# design.net
KiCad netlist of a schematic drawn in Altium Designer
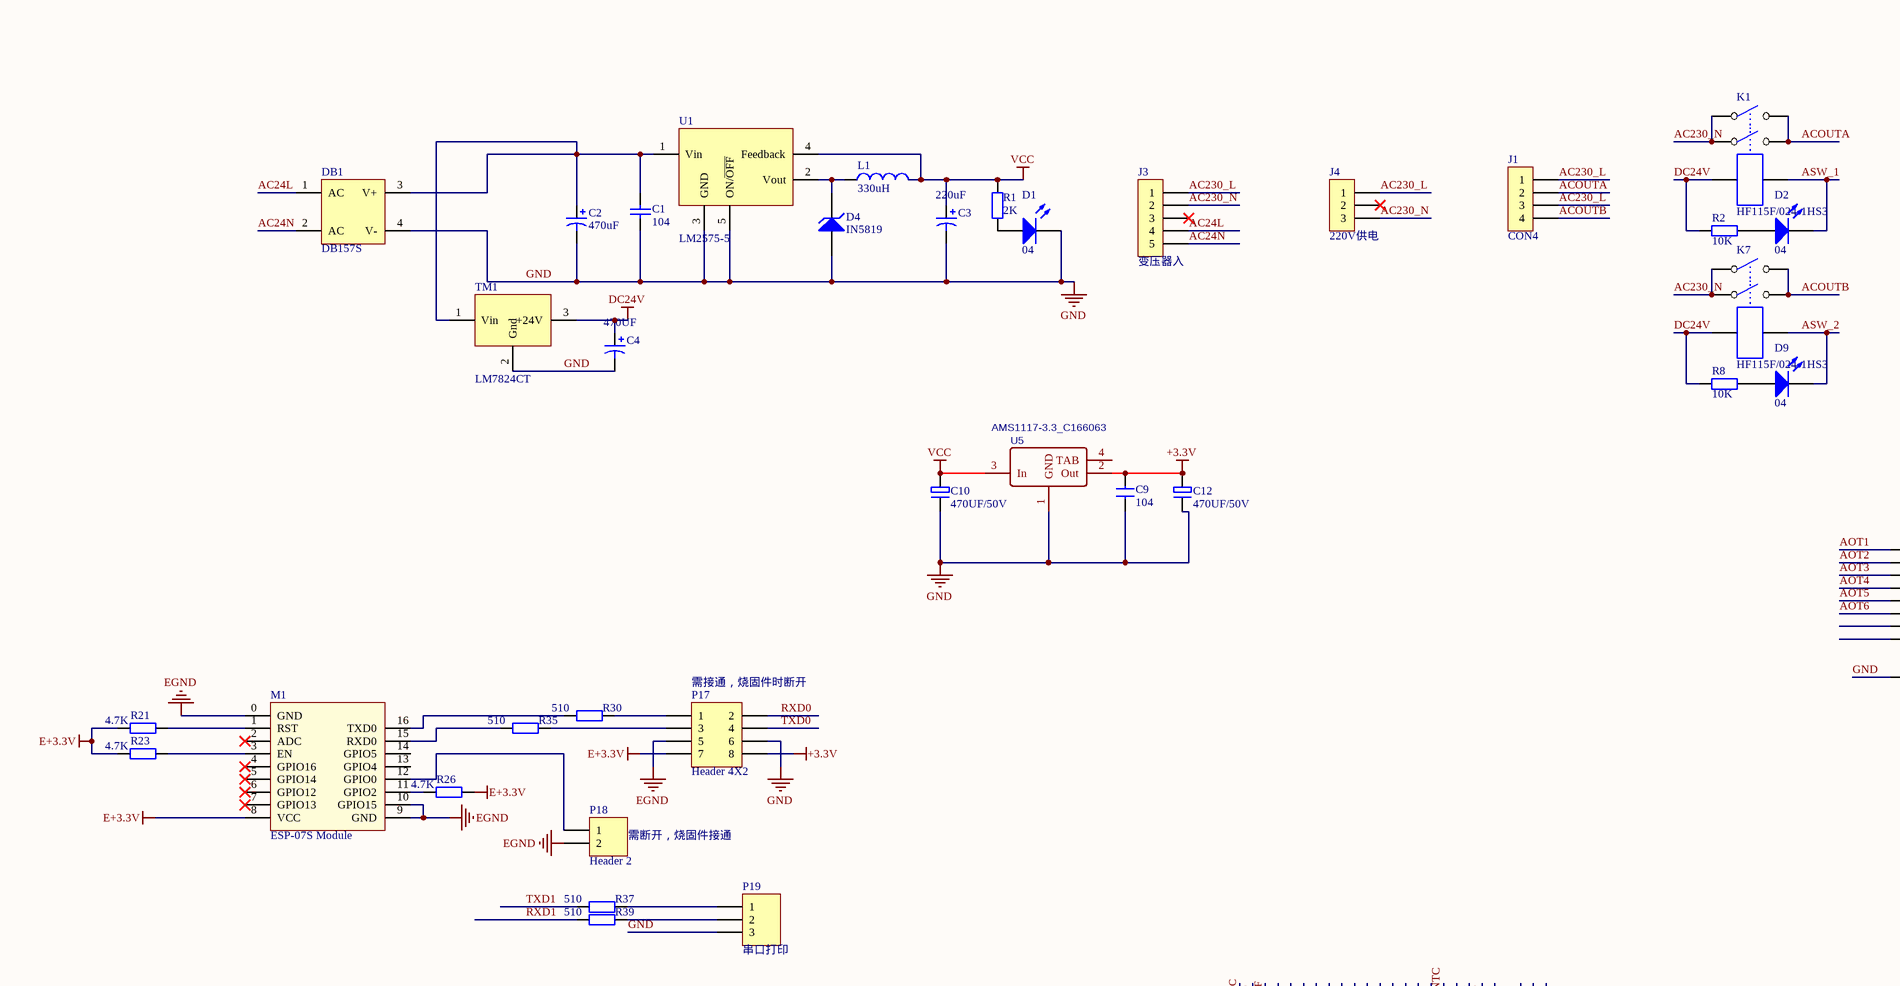
[diagram p0: 下程序炸炉.SchDoc, top left]
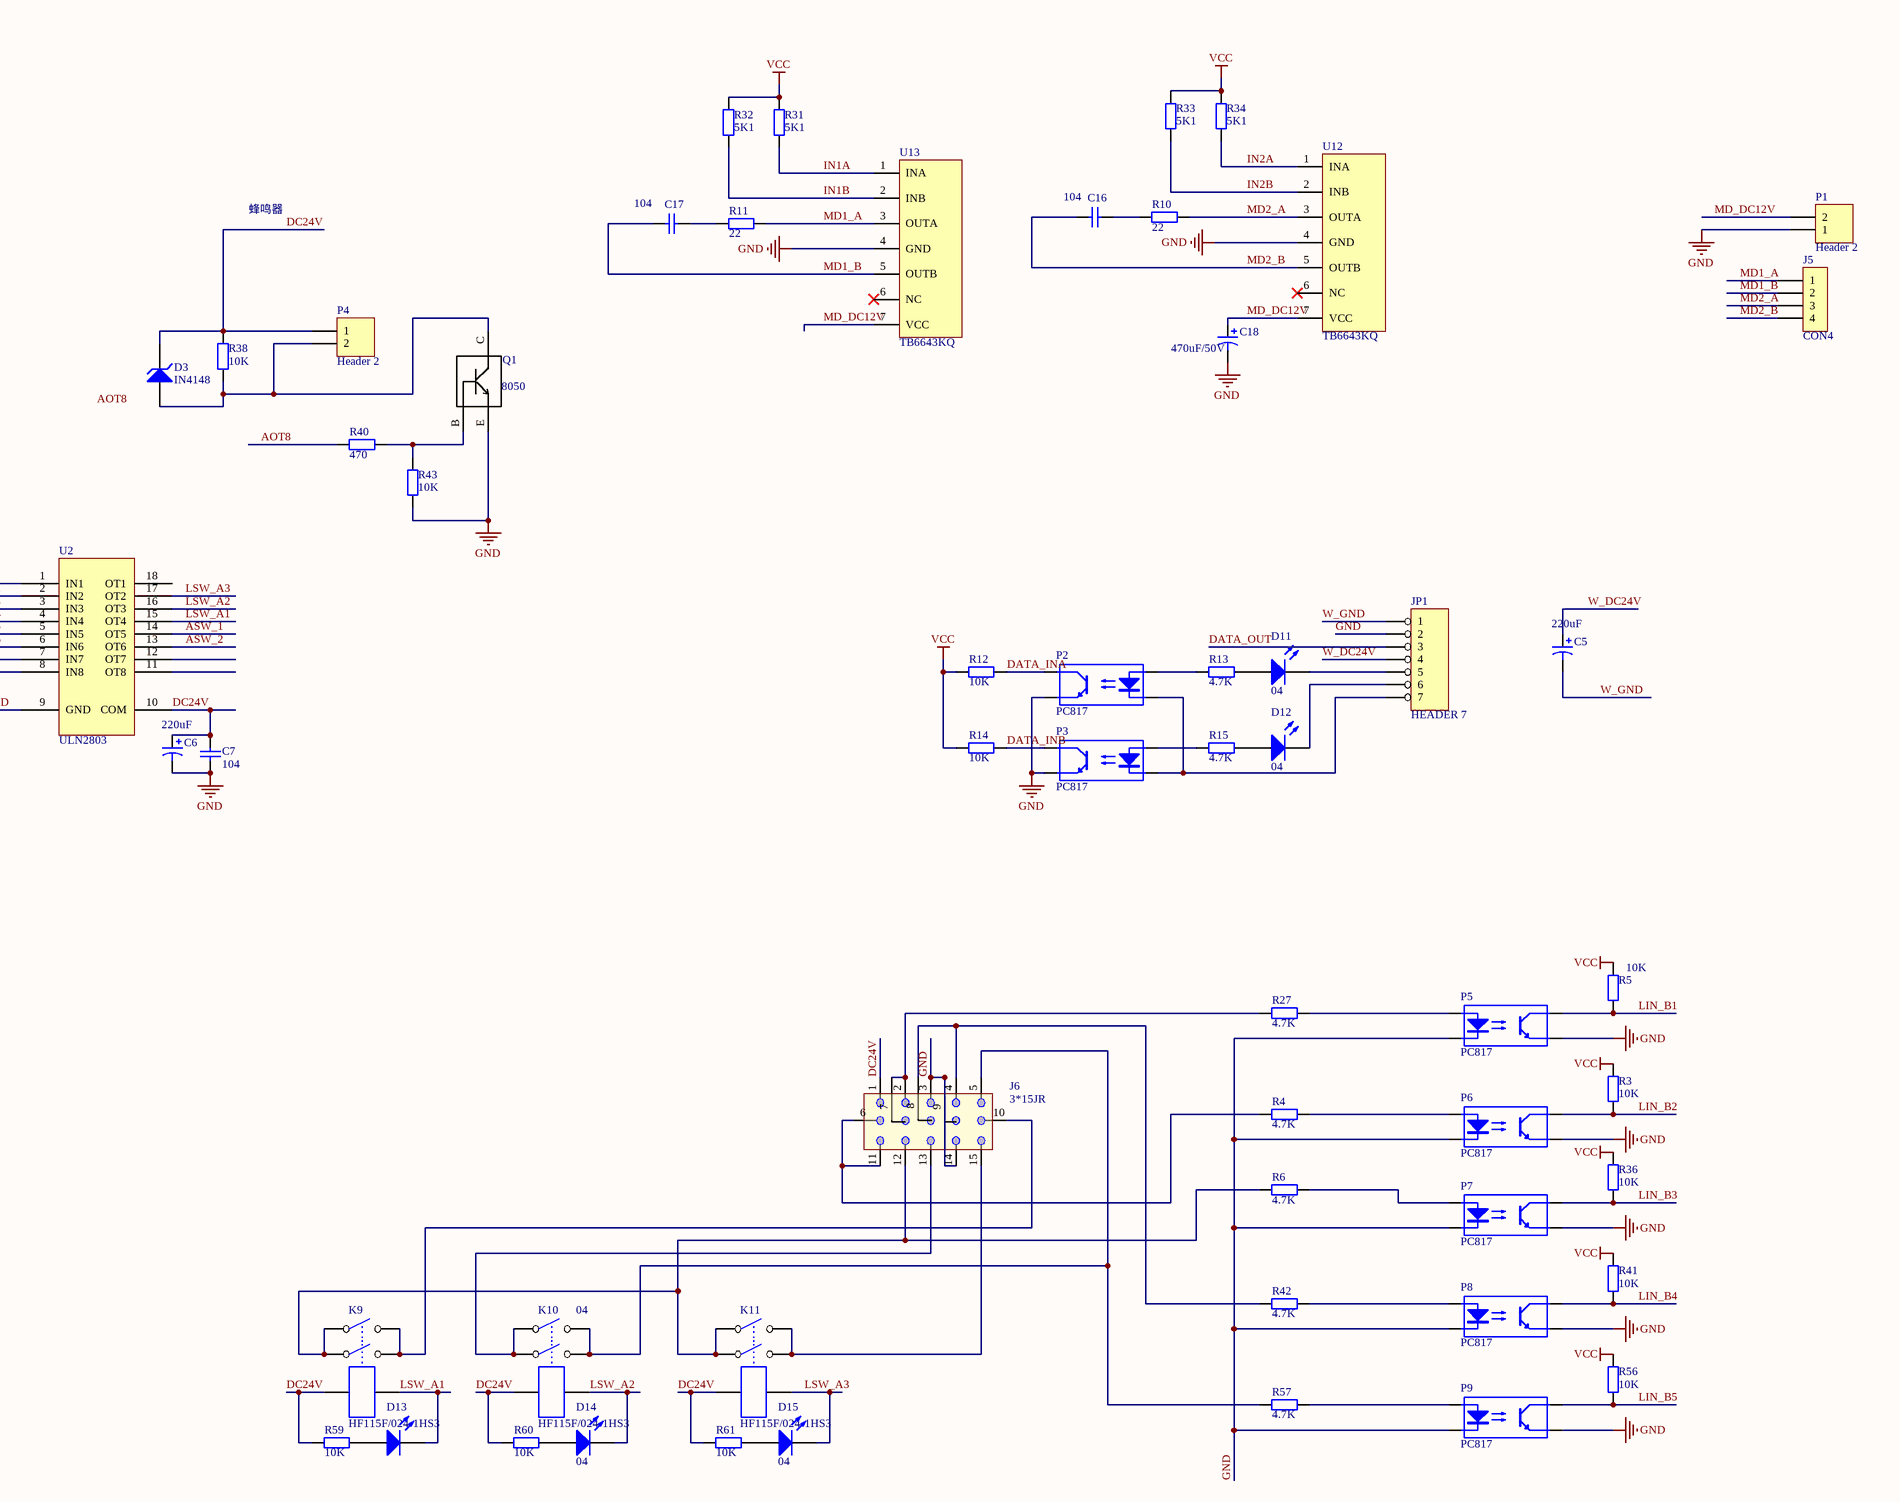
[diagram p1: 下程序炸炉.SchDoc, top right]
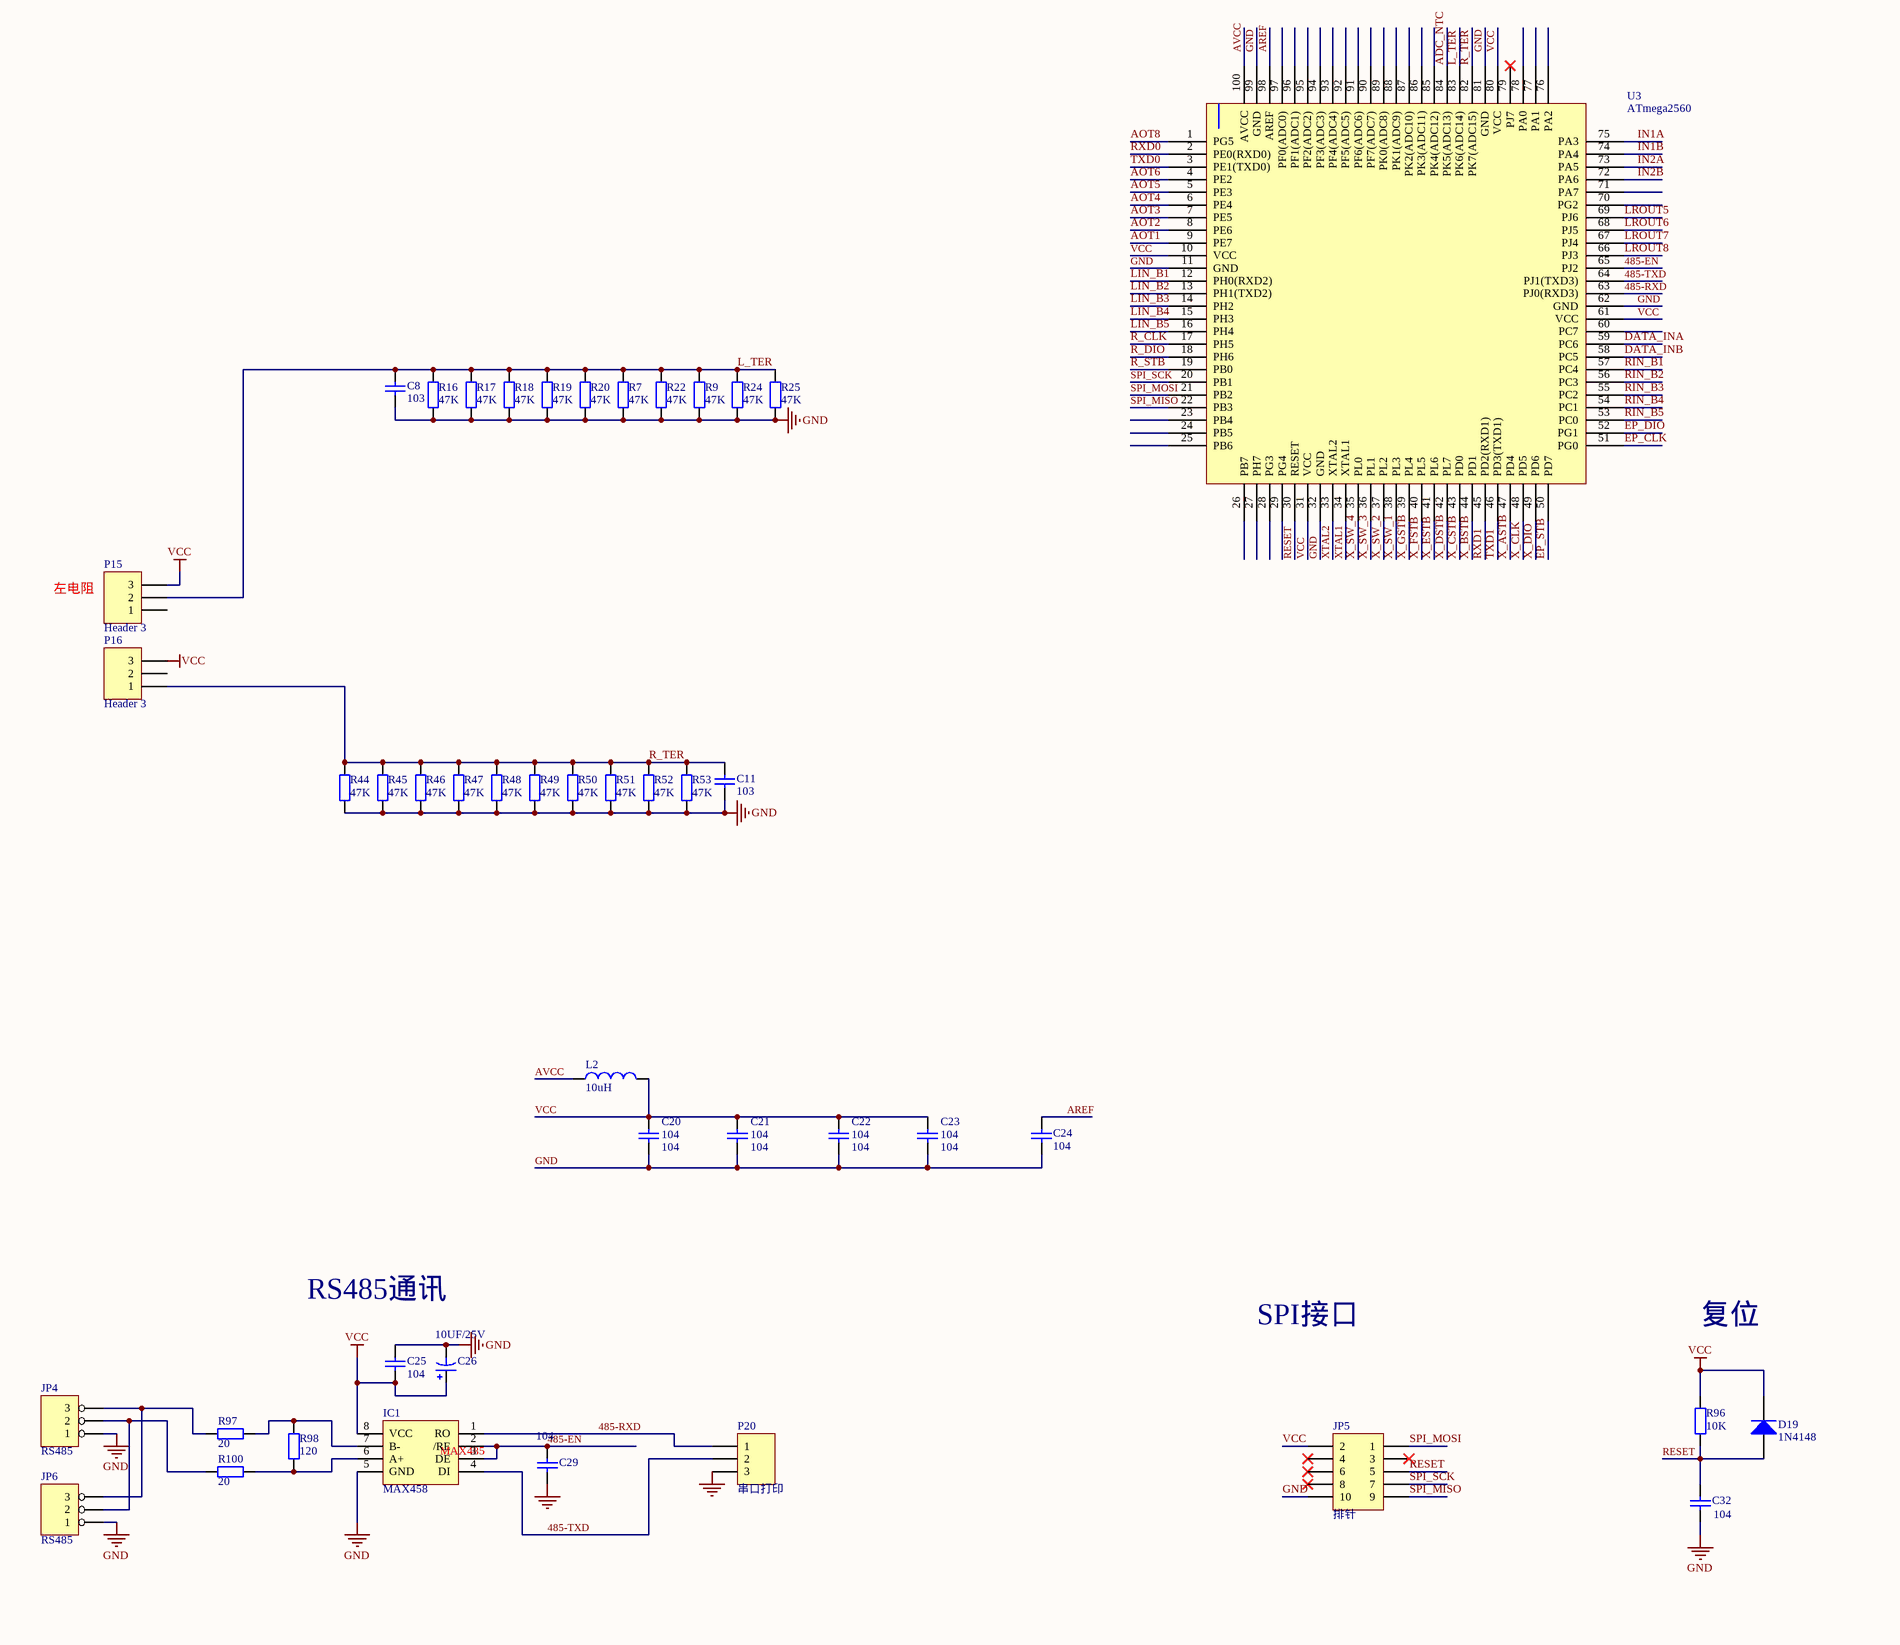
[diagram p2: 下程序炸炉.SchDoc, bottom left]
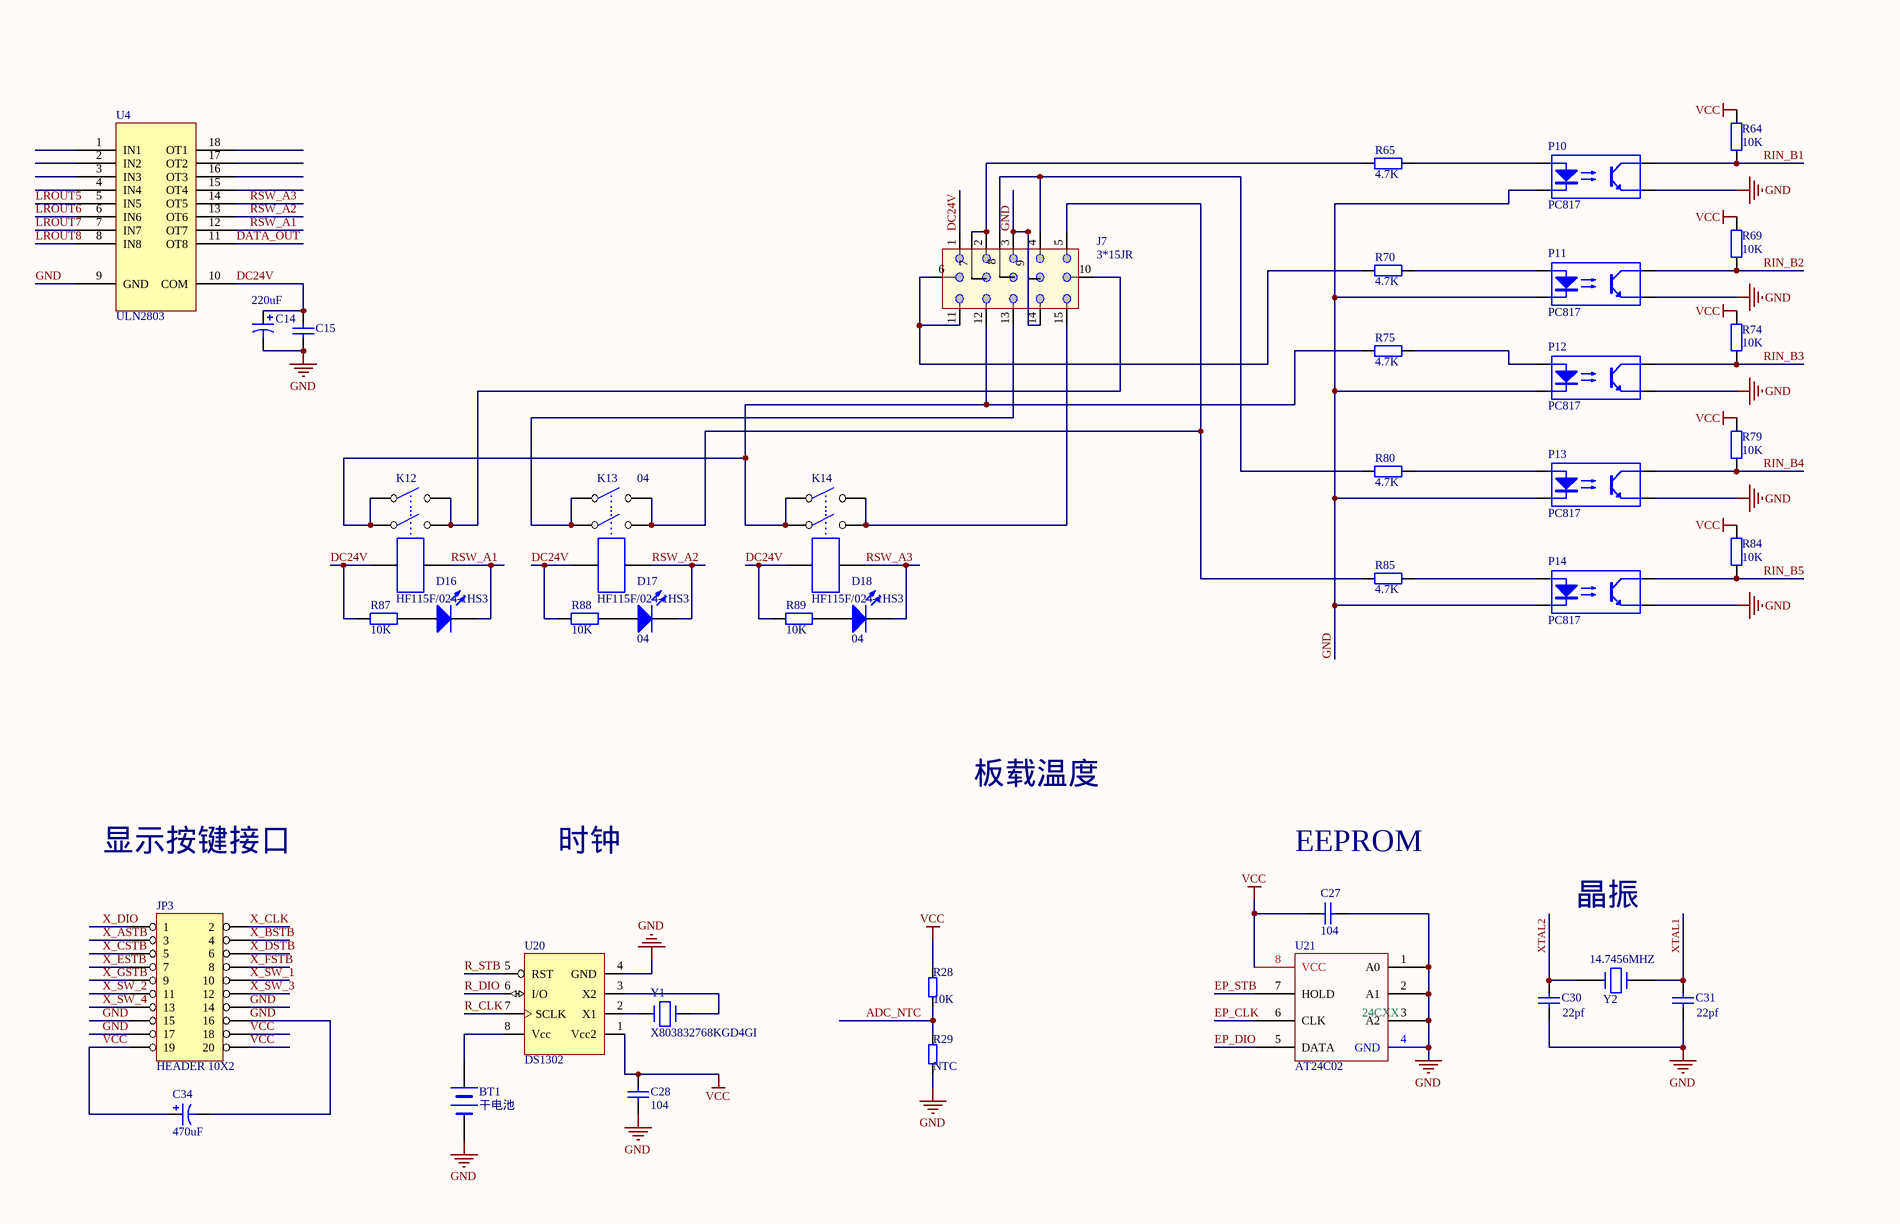
[diagram p3: 下程序炸炉.SchDoc, bottom right]

(export (version "E")
  (design (tool "Eeschema 10.0.6"))
  (components
    (comp (ref "BT1")
      (value "干电池")
      (footprint "PcbLib1:BAT-TH_BS-2-1")
      (description "Battery")
      (libsource (lib "电池及电源") (part "干电池"))
    )
    (comp (ref "C1")
      (value "104")
      (footprint "PcbLib1:0805")
      (description "Capacitor")
      (fields (field (name "PUBLISHER") "Altium Limited"))
      (libsource (lib "Miscellaneous Devices") (part "Cap"))
    )
    (comp (ref "C2")
      (value "470uF")
      (footprint "PcbLib1:CD9")
      (description "Polarized Capacitor (Radial)")
      (fields (field (name "Comment") "470UF/50V") (field (name "PUBLISHER") "Altium Limited"))
      (libsource (lib "Miscellaneous Devices") (part "Cap Pol1"))
    )
    (comp (ref "C3")
      (value "220uF")
      (footprint "PcbLib1:CD9")
      (description "Polarized Capacitor (Radial)")
      (fields (field (name "PUBLISHER") "Altium Limited"))
      (libsource (lib "Miscellaneous Devices") (part "Cap Pol1"))
    )
    (comp (ref "C4")
      (value "470UF")
      (footprint "PcbLib1:CD9")
      (description "Polarized Capacitor (Radial)")
      (fields (field (name "PUBLISHER") "Altium Limited"))
      (libsource (lib "Miscellaneous Devices") (part "Cap Pol1"))
    )
    (comp (ref "C5")
      (value "220uF")
      (footprint "PcbLib1:CD9")
      (description "Polarized Capacitor (Radial)")
      (fields (field (name "PUBLISHER") "Altium Limited"))
      (libsource (lib "Miscellaneous Devices") (part "Cap Pol1"))
    )
    (comp (ref "C6")
      (value "220uF")
      (footprint "PcbLib1:CD9")
      (description "Polarized Capacitor (Radial)")
      (fields (field (name "PUBLISHER") "Altium Limited"))
      (libsource (lib "Miscellaneous Devices") (part "Cap Pol1"))
    )
    (comp (ref "C7")
      (value "104")
      (footprint "PcbLib1:0805")
      (description "Capacitor")
      (fields (field (name "PUBLISHER") "Altium Limited"))
      (libsource (lib "Miscellaneous Devices") (part "Cap"))
    )
    (comp (ref "C8")
      (value "103")
      (footprint "PcbLib1:0805")
      (description "Capacitor")
      (fields (field (name "PUBLISHER") "Altium Limited"))
      (libsource (lib "Miscellaneous Devices") (part "Cap"))
    )
    (comp (ref "C9") (value "104") (footprint "PcbLib1:0805") (libsource (lib "Altium") (part "CAP")))
    (comp (ref "C10") (value "470UF/50V") (footprint "PcbLib1:CD9") (libsource (lib "Altium") (part "ECAP")))
    (comp (ref "C11")
      (value "103")
      (footprint "PcbLib1:0805")
      (description "Capacitor")
      (fields (field (name "PUBLISHER") "Altium Limited"))
      (libsource (lib "Miscellaneous Devices") (part "Cap"))
    )
    (comp (ref "C12") (value "470UF/50V") (footprint "PcbLib1:CD9") (libsource (lib "Altium") (part "ECAP")))
    (comp (ref "C14")
      (value "220uF")
      (footprint "PcbLib1:CD9")
      (description "Polarized Capacitor (Radial)")
      (fields (field (name "PUBLISHER") "Altium Limited"))
      (libsource (lib "Miscellaneous Devices") (part "Cap Pol1"))
    )
    (comp (ref "C15")
      (value "104")
      (footprint "PcbLib1:0805")
      (description "Capacitor")
      (fields (field (name "PUBLISHER") "Altium Limited"))
      (libsource (lib "Miscellaneous Devices") (part "Cap"))
    )
    (comp (ref "C16")
      (value "104")
      (footprint "PcbLib1:0805")
      (description "Capacitor")
      (fields (field (name "PUBLISHER") "Altium Limited"))
      (libsource (lib "Miscellaneous Devices") (part "Cap"))
    )
    (comp (ref "C17")
      (value "104")
      (footprint "PcbLib1:0805")
      (description "Capacitor")
      (fields (field (name "PUBLISHER") "Altium Limited"))
      (libsource (lib "Miscellaneous Devices") (part "Cap"))
    )
    (comp (ref "C18")
      (value "470uF/50V")
      (footprint "PcbLib1:CD9")
      (description "Polarized Capacitor (Radial)")
      (fields (field (name "PUBLISHER") "Altium Limited"))
      (libsource (lib "Miscellaneous Devices") (part "Cap Pol1"))
    )
    (comp (ref "C20")
      (value "104")
      (footprint "PcbLib1:0805")
      (description "Capacitor")
      (fields (field (name "ALTIUM_VALUE") "104") (field (name "PUBLISHER") "Altium Limited"))
      (libsource (lib "Miscellaneous Devices") (part "Cap"))
    )
    (comp (ref "C21")
      (value "104")
      (footprint "PcbLib1:0805")
      (description "Capacitor")
      (fields (field (name "ALTIUM_VALUE") "104") (field (name "PUBLISHER") "Altium Limited"))
      (libsource (lib "Miscellaneous Devices") (part "Cap"))
    )
    (comp (ref "C22")
      (value "104")
      (footprint "PcbLib1:0805")
      (description "Capacitor")
      (fields (field (name "ALTIUM_VALUE") "104") (field (name "PUBLISHER") "Altium Limited"))
      (libsource (lib "Miscellaneous Devices") (part "Cap"))
    )
    (comp (ref "C23")
      (value "104")
      (footprint "PcbLib1:0805")
      (description "Capacitor")
      (fields (field (name "ALTIUM_VALUE") "104") (field (name "PUBLISHER") "Altium Limited"))
      (libsource (lib "Miscellaneous Devices") (part "Cap"))
    )
    (comp (ref "C24")
      (value "104")
      (footprint "PcbLib1:0805")
      (description "Capacitor")
      (fields (field (name "PUBLISHER") "Altium Limited"))
      (libsource (lib "Miscellaneous Devices") (part "Cap"))
    )
    (comp (ref "C25")
      (value "104")
      (footprint "PcbLib1:0805")
      (description "Capacitor")
      (fields (field (name "PUBLISHER") "Altium Limited"))
      (libsource (lib "Miscellaneous Devices") (part "Cap"))
    )
    (comp (ref "C26")
      (value "10UF/25V")
      (footprint "PcbLib1:cap")
      (description "Polarized Capacitor (Radial)")
      (fields (field (name "PUBLISHER") "Altium Limited"))
      (libsource (lib "Miscellaneous Devices") (part "Cap Pol1"))
    )
    (comp (ref "C27")
      (value "104")
      (footprint "PcbLib1:0805")
      (description "Capacitor")
      (fields (field (name "PUBLISHER") "Altium Limited"))
      (libsource (lib "Miscellaneous Devices") (part "Cap"))
    )
    (comp (ref "C28")
      (value "104")
      (footprint "PcbLib1:0805")
      (description "Capacitor")
      (fields (field (name "PUBLISHER") "Altium Limited"))
      (libsource (lib "Miscellaneous Devices") (part "Cap"))
    )
    (comp (ref "C29")
      (value "104")
      (footprint "PcbLib1:0805")
      (description "Capacitor")
      (fields (field (name "PUBLISHER") "Altium Limited"))
      (libsource (lib "Miscellaneous Devices") (part "Cap"))
    )
    (comp (ref "C30")
      (value "22pf")
      (footprint "PcbLib1:0805")
      (description "Capacitor")
      (fields (field (name "PUBLISHER") "Altium Limited"))
      (libsource (lib "Miscellaneous Devices") (part "Cap"))
    )
    (comp (ref "C31")
      (value "22pf")
      (footprint "PcbLib1:0805")
      (description "Capacitor")
      (fields (field (name "PUBLISHER") "Altium Limited"))
      (libsource (lib "Miscellaneous Devices") (part "Cap"))
    )
    (comp (ref "C32")
      (value "104")
      (footprint "PcbLib1:0805")
      (description "Capacitor")
      (fields (field (name "PUBLISHER") "Altium Limited"))
      (libsource (lib "Miscellaneous Devices") (part "Cap"))
    )
    (comp (ref "C34")
      (value "470uF")
      (footprint "PcbLib1:CD9")
      (description "Polarized Capacitor (Radial)")
      (fields (field (name "Comment") "470UF/50V") (field (name "PUBLISHER") "Altium Limited"))
      (libsource (lib "Miscellaneous Devices") (part "Cap Pol1"))
    )
    (comp (ref "D1")
      (value "04")
      (footprint "PcbLib1:LED-T")
      (description "Typical INFRARED GaAs LED")
      (fields (field (name "PUBLISHER") "Altium Limited"))
      (libsource (lib "Miscellaneous Devices") (part "LED0"))
    )
    (comp (ref "D2")
      (value "04")
      (footprint "PcbLib1:LED-T")
      (description "Typical INFRARED GaAs LED")
      (fields (field (name "PUBLISHER") "Altium Limited"))
      (libsource (lib "Miscellaneous Devices") (part "LED0"))
    )
    (comp (ref "D3")
      (value "IN4148")
      (footprint "PcbLib1:DO-214AC")
      (description "Zener Diode")
      (fields (field (name "PUBLISHER") "Altium Limited"))
      (libsource (lib "Miscellaneous Devices") (part "D Zener"))
    )
    (comp (ref "D4")
      (value "IN5819")
      (footprint "PcbLib1:DO-214AC")
      (description "Zener Diode")
      (fields (field (name "PUBLISHER") "Altium Limited"))
      (libsource (lib "Miscellaneous Devices") (part "D Zener"))
    )
    (comp (ref "D9")
      (value "04")
      (footprint "PcbLib1:LED-T")
      (description "Typical INFRARED GaAs LED")
      (fields (field (name "PUBLISHER") "Altium Limited"))
      (libsource (lib "Miscellaneous Devices") (part "LED0"))
    )
    (comp (ref "D11")
      (value "04")
      (footprint "PcbLib1:LED-T")
      (description "Typical INFRARED GaAs LED")
      (fields (field (name "PUBLISHER") "Altium Limited"))
      (libsource (lib "Miscellaneous Devices") (part "LED0"))
    )
    (comp (ref "D12")
      (value "04")
      (footprint "PcbLib1:LED-T")
      (description "Typical INFRARED GaAs LED")
      (fields (field (name "PUBLISHER") "Altium Limited"))
      (libsource (lib "Miscellaneous Devices") (part "LED0"))
    )
    (comp (ref "D13")
      (value "04")
      (footprint "PcbLib1:LED-T")
      (description "Typical INFRARED GaAs LED")
      (fields (field (name "PUBLISHER") "Altium Limited"))
      (libsource (lib "Miscellaneous Devices") (part "LED0"))
    )
    (comp (ref "D14")
      (value "04")
      (footprint "PcbLib1:LED-T")
      (description "Typical INFRARED GaAs LED")
      (fields (field (name "PUBLISHER") "Altium Limited"))
      (libsource (lib "Miscellaneous Devices") (part "LED0"))
    )
    (comp (ref "D15")
      (value "04")
      (footprint "PcbLib1:LED-T")
      (description "Typical INFRARED GaAs LED")
      (fields (field (name "PUBLISHER") "Altium Limited"))
      (libsource (lib "Miscellaneous Devices") (part "LED0"))
    )
    (comp (ref "D16")
      (value "04")
      (footprint "PcbLib1:LED-T")
      (description "Typical INFRARED GaAs LED")
      (fields (field (name "PUBLISHER") "Altium Limited"))
      (libsource (lib "Miscellaneous Devices") (part "LED0"))
    )
    (comp (ref "D17")
      (value "04")
      (footprint "PcbLib1:LED-T")
      (description "Typical INFRARED GaAs LED")
      (fields (field (name "PUBLISHER") "Altium Limited"))
      (libsource (lib "Miscellaneous Devices") (part "LED0"))
    )
    (comp (ref "D18")
      (value "04")
      (footprint "PcbLib1:LED-T")
      (description "Typical INFRARED GaAs LED")
      (fields (field (name "PUBLISHER") "Altium Limited"))
      (libsource (lib "Miscellaneous Devices") (part "LED0"))
    )
    (comp (ref "D19")
      (value "1N4148")
      (footprint "PcbLib1:DO-214AC")
      (description "High Conductance Fast Diode")
      (fields (field (name "PUBLISHER") "Altium Limited"))
      (libsource (lib "ATmega169_1") (part "Diode 1N4148"))
    )
    (comp (ref "DB1")
      (value "DB157S")
      (footprint "PcbLib1:LC-GBU")
      (libsource (lib "常用元件库") (part "BRIDGE2"))
    )
    (comp (ref "IC1")
      (value "MAX458")
      (footprint "PcbLib1:SOIC-8_150mil")
      (libsource (lib "GBY的原理图库") (part "MAX485"))
    )
    (comp (ref "J1")
      (value "CON4")
      (footprint "PcbLib1:4PIN-6.3")
      (description "Connector")
      (libsource (lib "Miscellaneous Devices") (part "CON4"))
    )
    (comp (ref "J3")
      (value "变压器入")
      (footprint "PcbLib1:5PIN-6.3")
      (description "Connector")
      (libsource (lib "Miscellaneous Devices") (part "CON5"))
    )
    (comp (ref "J4")
      (value "220V供电")
      (footprint "PcbLib1:3PIN-6.3")
      (description "Connector")
      (libsource (lib "Miscellaneous Devices") (part "CON3"))
    )
    (comp (ref "J5")
      (value "CON4")
      (footprint "PcbLib1:4PIN 3.96")
      (description "Connector")
      (libsource (lib "") (part "CON4_1"))
    )
    (comp (ref "J6")
      (value "3*15JR")
      (footprint "PcbLib1:3*5PIN-6.3")
      (libsource (lib "Schlib1") (part "Component_1"))
    )
    (comp (ref "J7")
      (value "3*15JR")
      (footprint "PcbLib1:3*5PIN-6.3")
      (libsource (lib "Schlib1") (part "Component_1"))
    )
    (comp (ref "JP1")
      (value "HEADER 7")
      (footprint "PcbLib1:7PIN 3.96")
      (libsource (lib "Miscellaneous Devices") (part "HEADER 7"))
    )
    (comp (ref "JP3")
      (value "HEADER 10X2")
      (footprint "PcbLib1:HDR2X10")
      (libsource (lib "Miscellaneous Devices") (part "HEADER 10X2"))
    )
    (comp (ref "JP4")
      (value "RS485")
      (footprint "PcbLib1:3PIN 3.96")
      (libsource (lib "Miscellaneous Devices") (part "HEADER 3"))
    )
    (comp (ref "JP5")
      (value "排针")
      (footprint "PcbLib1:HDR2X5 - duplicate - duplicate")
      (description "Header, 5-Pin, Dual row")
      (fields (field (name "PUBLISHER") "Altium Limited"))
      (libsource (lib "Schlib1") (part "Header 5X2"))
    )
    (comp (ref "JP6")
      (value "RS485")
      (footprint "PcbLib1:3PIN 3.96")
      (libsource (lib "Miscellaneous Devices") (part "HEADER 3"))
    )
    (comp (ref "K1")
      (value "HF115F/024-1HS3")
      (footprint "PcbLib1:HF115FA")
      (libsource (lib "Miscellaneous Devices") (part "RELAY-DPST"))
    )
    (comp (ref "K7")
      (value "HF115F/024-1HS3")
      (footprint "PcbLib1:HF115FA")
      (libsource (lib "Miscellaneous Devices") (part "RELAY-DPST"))
    )
    (comp (ref "K9")
      (value "HF115F/024-1HS3")
      (footprint "PcbLib1:HF115FA")
      (libsource (lib "Miscellaneous Devices") (part "RELAY-DPST"))
    )
    (comp (ref "K10")
      (value "HF115F/024-1HS3")
      (footprint "PcbLib1:HF115FA")
      (libsource (lib "Miscellaneous Devices") (part "RELAY-DPST"))
    )
    (comp (ref "K11")
      (value "HF115F/024-1HS3")
      (footprint "PcbLib1:HF115FA")
      (libsource (lib "Miscellaneous Devices") (part "RELAY-DPST"))
    )
    (comp (ref "K12")
      (value "HF115F/024-1HS3")
      (footprint "PcbLib1:HF115FA")
      (libsource (lib "Miscellaneous Devices") (part "RELAY-DPST"))
    )
    (comp (ref "K13")
      (value "HF115F/024-1HS3")
      (footprint "PcbLib1:HF115FA")
      (libsource (lib "Miscellaneous Devices") (part "RELAY-DPST"))
    )
    (comp (ref "K14")
      (value "HF115F/024-1HS3")
      (footprint "PcbLib1:HF115FA")
      (libsource (lib "Miscellaneous Devices") (part "RELAY-DPST"))
    )
    (comp (ref "L1")
      (value "330uH")
      (footprint "PcbLib1:SMD331")
      (description "Inductor")
      (fields (field (name "PUBLISHER") "Altium Limited"))
      (libsource (lib "Miscellaneous Devices") (part "Inductor"))
    )
    (comp (ref "L2")
      (value "10uH")
      (footprint "常用元件封装:1206")
      (description "Inductor")
      (fields (field (name "PUBLISHER") "Altium Limited"))
      (libsource (lib "Miscellaneous Devices") (part "Inductor"))
    )
    (comp (ref "M1")
      (value "ESP-07S Module")
      (footprint "PcbLib1:ESP-07S Module")
      (libsource (lib "ESP-07S Module") (part "ESP-07S Module"))
    )
    (comp (ref "P1")
      (value "Header 2")
      (footprint "PcbLib1:2PIN 3.96")
      (description "Header, 2-Pin")
      (fields (field (name "PUBLISHER") "Altium Limited"))
      (libsource (lib "") (part "Header 2_1"))
    )
    (comp (ref "P2") (value "PC817") (footprint "PcbLib1:LC-SMD-4") (libsource (lib "") (part "P521_1")))
    (comp (ref "P3") (value "PC817") (footprint "PcbLib1:LC-SMD-4") (libsource (lib "") (part "P521_1")))
    (comp (ref "P4")
      (value "Header 2")
      (footprint "PcbLib1:2PIN 3.96")
      (description "Header, 2-Pin")
      (fields (field (name "PUBLISHER") "Altium Limited"))
      (libsource (lib "Miscellaneous Connectors") (part "Header 2"))
    )
    (comp (ref "P5") (value "PC817") (footprint "PcbLib1:LC-SMD-4") (libsource (lib "常用元件库") (part "P521")))
    (comp (ref "P6") (value "PC817") (footprint "PcbLib1:LC-SMD-4") (libsource (lib "常用元件库") (part "P521")))
    (comp (ref "P7") (value "PC817") (footprint "PcbLib1:LC-SMD-4") (libsource (lib "常用元件库") (part "P521")))
    (comp (ref "P8") (value "PC817") (footprint "PcbLib1:LC-SMD-4") (libsource (lib "常用元件库") (part "P521")))
    (comp (ref "P9") (value "PC817") (footprint "PcbLib1:LC-SMD-4") (libsource (lib "常用元件库") (part "P521")))
    (comp (ref "P10") (value "PC817") (footprint "PcbLib1:LC-SMD-4") (libsource (lib "常用元件库") (part "P521")))
    (comp (ref "P11") (value "PC817") (footprint "PcbLib1:LC-SMD-4") (libsource (lib "常用元件库") (part "P521")))
    (comp (ref "P12") (value "PC817") (footprint "PcbLib1:LC-SMD-4") (libsource (lib "常用元件库") (part "P521")))
    (comp (ref "P13") (value "PC817") (footprint "PcbLib1:LC-SMD-4") (libsource (lib "常用元件库") (part "P521")))
    (comp (ref "P14") (value "PC817") (footprint "PcbLib1:LC-SMD-4") (libsource (lib "常用元件库") (part "P521")))
    (comp (ref "P15")
      (value "Header 3")
      (footprint "PcbLib1:3PIN 3.96")
      (description "Header, 3-Pin")
      (fields (field (name "PUBLISHER") "Altium Limited"))
      (libsource (lib "") (part "Header 3_1"))
    )
    (comp (ref "P16")
      (value "Header 3")
      (footprint "PcbLib1:3PIN 3.96")
      (description "Header, 3-Pin")
      (fields (field (name "PUBLISHER") "Altium Limited"))
      (libsource (lib "") (part "Header 3_1"))
    )
    (comp (ref "P17")
      (value "Header 4X2")
      (footprint "Miscellaneous Connectors:HDR2X4")
      (description "Header, 4-Pin, Dual row")
      (fields (field (name "PUBLISHER") "Altium Limited"))
      (libsource (lib "Miscellaneous Connectors") (part "Header 4X2"))
    )
    (comp (ref "P18")
      (value "Header 2")
      (footprint "HDR1X2")
      (description "Header, 2-Pin")
      (fields (field (name "PUBLISHER") "Altium Limited"))
      (libsource (lib "Miscellaneous Connectors") (part "Header 2"))
    )
    (comp (ref "P19")
      (value "串口打印")
      (footprint "HDR1X3")
      (description "Header, 3-Pin")
      (fields (field (name "PUBLISHER") "Altium Limited"))
      (libsource (lib "Miscellaneous Connectors") (part "Header 3"))
    )
    (comp (ref "P20")
      (value "串口打印")
      (footprint "HDR1X3")
      (description "Header, 3-Pin")
      (fields (field (name "PUBLISHER") "Altium Limited"))
      (libsource (lib "Miscellaneous Connectors") (part "Header 3"))
    )
    (comp (ref "Q1")
      (value "8050")
      (footprint "PcbLib1:SOT-23 - duplicate")
      (libsource (lib "Schlib1") (part "BC817-8050"))
    )
    (comp (ref "R1")
      (value "2K")
      (footprint "PcbLib1:0805")
      (description "Resistor")
      (fields (field (name "PUBLISHER") "Altium Limited"))
      (libsource (lib "Miscellaneous Devices") (part "Res2"))
    )
    (comp (ref "R2")
      (value "10K")
      (footprint "PcbLib1:0805")
      (description "Resistor")
      (fields (field (name "Comment") "10k") (field (name "PUBLISHER") "Altium Limited"))
      (libsource (lib "") (part "Res2_1"))
    )
    (comp (ref "R3")
      (value "10K")
      (footprint "PcbLib1:0805")
      (description "Resistor")
      (fields (field (name "Comment") "10k") (field (name "PUBLISHER") "Altium Limited"))
      (libsource (lib "Miscellaneous Devices") (part "Res2"))
    )
    (comp (ref "R4")
      (value "4.7K")
      (footprint "PcbLib1:0805")
      (description "Resistor")
      (fields (field (name "PUBLISHER") "Altium Limited"))
      (libsource (lib "") (part "Res2_2"))
    )
    (comp (ref "R5")
      (value "10K")
      (footprint "PcbLib1:0805")
      (description "Resistor")
      (fields (field (name "Comment") "10k") (field (name "PUBLISHER") "Altium Limited"))
      (libsource (lib "Miscellaneous Devices") (part "Res2"))
    )
    (comp (ref "R6")
      (value "4.7K")
      (footprint "PcbLib1:0805")
      (description "Resistor")
      (fields (field (name "PUBLISHER") "Altium Limited"))
      (libsource (lib "") (part "Res2_2"))
    )
    (comp (ref "R7")
      (value "47K")
      (footprint "PcbLib1:0805")
      (description "Resistor")
      (fields (field (name "PUBLISHER") "Altium Limited"))
      (libsource (lib "Miscellaneous Devices") (part "Res2"))
    )
    (comp (ref "R8")
      (value "10K")
      (footprint "PcbLib1:0805")
      (description "Resistor")
      (fields (field (name "Comment") "10k") (field (name "PUBLISHER") "Altium Limited"))
      (libsource (lib "") (part "Res2_1"))
    )
    (comp (ref "R9")
      (value "47K")
      (footprint "PcbLib1:0805")
      (description "Resistor")
      (fields (field (name "PUBLISHER") "Altium Limited"))
      (libsource (lib "Miscellaneous Devices") (part "Res2"))
    )
    (comp (ref "R10")
      (value "22")
      (footprint "PcbLib1:1206")
      (description "Resistor")
      (fields (field (name "PUBLISHER") "Altium Limited"))
      (libsource (lib "") (part "Res2_1"))
    )
    (comp (ref "R11")
      (value "22")
      (footprint "PcbLib1:1206")
      (description "Resistor")
      (fields (field (name "PUBLISHER") "Altium Limited"))
      (libsource (lib "") (part "Res2_1"))
    )
    (comp (ref "R12")
      (value "10K")
      (footprint "PcbLib1:0805")
      (description "Resistor")
      (fields (field (name "Comment") "10k") (field (name "PUBLISHER") "Altium Limited"))
      (libsource (lib "") (part "Res2_2"))
    )
    (comp (ref "R13")
      (value "4.7K")
      (footprint "PcbLib1:0805")
      (description "Resistor")
      (fields (field (name "PUBLISHER") "Altium Limited"))
      (libsource (lib "") (part "Res2_1"))
    )
    (comp (ref "R14")
      (value "10K")
      (footprint "PcbLib1:0805")
      (description "Resistor")
      (fields (field (name "Comment") "10k") (field (name "PUBLISHER") "Altium Limited"))
      (libsource (lib "") (part "Res2_2"))
    )
    (comp (ref "R15")
      (value "4.7K")
      (footprint "PcbLib1:0805")
      (description "Resistor")
      (fields (field (name "PUBLISHER") "Altium Limited"))
      (libsource (lib "") (part "Res2_1"))
    )
    (comp (ref "R16")
      (value "47K")
      (footprint "PcbLib1:0805")
      (description "Resistor")
      (fields (field (name "PUBLISHER") "Altium Limited"))
      (libsource (lib "Miscellaneous Devices") (part "Res2"))
    )
    (comp (ref "R17")
      (value "47K")
      (footprint "PcbLib1:0805")
      (description "Resistor")
      (fields (field (name "PUBLISHER") "Altium Limited"))
      (libsource (lib "Miscellaneous Devices") (part "Res2"))
    )
    (comp (ref "R18")
      (value "47K")
      (footprint "PcbLib1:0805")
      (description "Resistor")
      (fields (field (name "PUBLISHER") "Altium Limited"))
      (libsource (lib "Miscellaneous Devices") (part "Res2"))
    )
    (comp (ref "R19")
      (value "47K")
      (footprint "PcbLib1:0805")
      (description "Resistor")
      (fields (field (name "PUBLISHER") "Altium Limited"))
      (libsource (lib "Miscellaneous Devices") (part "Res2"))
    )
    (comp (ref "R20")
      (value "47K")
      (footprint "PcbLib1:0805")
      (description "Resistor")
      (fields (field (name "PUBLISHER") "Altium Limited"))
      (libsource (lib "Miscellaneous Devices") (part "Res2"))
    )
    (comp (ref "R21")
      (value "4.7K")
      (footprint "PcbLib1:0805")
      (description "Resistor")
      (fields (field (name "PUBLISHER") "Altium Limited"))
      (libsource (lib "") (part "Res2_1"))
    )
    (comp (ref "R22")
      (value "47K")
      (footprint "PcbLib1:0805")
      (description "Resistor")
      (fields (field (name "PUBLISHER") "Altium Limited"))
      (libsource (lib "Miscellaneous Devices") (part "Res2"))
    )
    (comp (ref "R23")
      (value "4.7K")
      (footprint "PcbLib1:0805")
      (description "Resistor")
      (fields (field (name "PUBLISHER") "Altium Limited"))
      (libsource (lib "") (part "Res2_1"))
    )
    (comp (ref "R24")
      (value "47K")
      (footprint "PcbLib1:0805")
      (description "Resistor")
      (fields (field (name "PUBLISHER") "Altium Limited"))
      (libsource (lib "Miscellaneous Devices") (part "Res2"))
    )
    (comp (ref "R25")
      (value "47K")
      (footprint "PcbLib1:0805")
      (description "Resistor")
      (fields (field (name "PUBLISHER") "Altium Limited"))
      (libsource (lib "Miscellaneous Devices") (part "Res2"))
    )
    (comp (ref "R26")
      (value "4.7K")
      (footprint "PcbLib1:0805")
      (description "Resistor")
      (fields (field (name "PUBLISHER") "Altium Limited"))
      (libsource (lib "") (part "Res2_1"))
    )
    (comp (ref "R27")
      (value "4.7K")
      (footprint "PcbLib1:0805")
      (description "Resistor")
      (fields (field (name "PUBLISHER") "Altium Limited"))
      (libsource (lib "") (part "Res2_2"))
    )
    (comp (ref "R28") (value "10K") (footprint "PcbLib1:0805") (libsource (lib "Altium") (part "RES")))
    (comp (ref "R29") (value "NTC") (footprint "PcbLib1:0805") (libsource (lib "Altium") (part "RES")))
    (comp (ref "R30")
      (value "510")
      (footprint "PcbLib1:0805")
      (description "Resistor")
      (fields (field (name "PUBLISHER") "Altium Limited"))
      (libsource (lib "") (part "Res2_1"))
    )
    (comp (ref "R31")
      (value "5K1")
      (footprint "PcbLib1:0805")
      (description "Resistor")
      (fields (field (name "PUBLISHER") "Altium Limited"))
      (libsource (lib "Miscellaneous Devices") (part "Res2"))
    )
    (comp (ref "R32")
      (value "5K1")
      (footprint "PcbLib1:0805")
      (description "Resistor")
      (fields (field (name "PUBLISHER") "Altium Limited"))
      (libsource (lib "Miscellaneous Devices") (part "Res2"))
    )
    (comp (ref "R33")
      (value "5K1")
      (footprint "PcbLib1:0805")
      (description "Resistor")
      (fields (field (name "PUBLISHER") "Altium Limited"))
      (libsource (lib "Miscellaneous Devices") (part "Res2"))
    )
    (comp (ref "R34")
      (value "5K1")
      (footprint "PcbLib1:0805")
      (description "Resistor")
      (fields (field (name "PUBLISHER") "Altium Limited"))
      (libsource (lib "Miscellaneous Devices") (part "Res2"))
    )
    (comp (ref "R35")
      (value "510")
      (footprint "PcbLib1:0805")
      (description "Resistor")
      (fields (field (name "PUBLISHER") "Altium Limited"))
      (libsource (lib "") (part "Res2_1"))
    )
    (comp (ref "R36")
      (value "10K")
      (footprint "PcbLib1:0805")
      (description "Resistor")
      (fields (field (name "Comment") "10k") (field (name "PUBLISHER") "Altium Limited"))
      (libsource (lib "Miscellaneous Devices") (part "Res2"))
    )
    (comp (ref "R37")
      (value "510")
      (footprint "PcbLib1:0805")
      (description "Resistor")
      (fields (field (name "PUBLISHER") "Altium Limited"))
      (libsource (lib "") (part "Res2_1"))
    )
    (comp (ref "R38")
      (value "10K")
      (footprint "0805")
      (description "Resistor")
      (fields (field (name "PUBLISHER") "Altium Limited"))
      (libsource (lib "Miscellaneous Devices") (part "Res2"))
    )
    (comp (ref "R39")
      (value "510")
      (footprint "PcbLib1:0805")
      (description "Resistor")
      (fields (field (name "PUBLISHER") "Altium Limited"))
      (libsource (lib "") (part "Res2_1"))
    )
    (comp (ref "R40")
      (value "470")
      (footprint "0805")
      (description "Resistor")
      (fields (field (name "PUBLISHER") "Altium Limited"))
      (libsource (lib "") (part "Res2_2"))
    )
    (comp (ref "R41")
      (value "10K")
      (footprint "PcbLib1:0805")
      (description "Resistor")
      (fields (field (name "Comment") "10k") (field (name "PUBLISHER") "Altium Limited"))
      (libsource (lib "Miscellaneous Devices") (part "Res2"))
    )
    (comp (ref "R42")
      (value "4.7K")
      (footprint "PcbLib1:0805")
      (description "Resistor")
      (fields (field (name "PUBLISHER") "Altium Limited"))
      (libsource (lib "") (part "Res2_2"))
    )
    (comp (ref "R43")
      (value "10K")
      (footprint "0805")
      (description "Resistor")
      (fields (field (name "PUBLISHER") "Altium Limited"))
      (libsource (lib "Miscellaneous Devices") (part "Res2"))
    )
    (comp (ref "R44")
      (value "47K")
      (footprint "PcbLib1:0805")
      (description "Resistor")
      (fields (field (name "PUBLISHER") "Altium Limited"))
      (libsource (lib "Miscellaneous Devices") (part "Res2"))
    )
    (comp (ref "R45")
      (value "47K")
      (footprint "PcbLib1:0805")
      (description "Resistor")
      (fields (field (name "PUBLISHER") "Altium Limited"))
      (libsource (lib "Miscellaneous Devices") (part "Res2"))
    )
    (comp (ref "R46")
      (value "47K")
      (footprint "PcbLib1:0805")
      (description "Resistor")
      (fields (field (name "PUBLISHER") "Altium Limited"))
      (libsource (lib "Miscellaneous Devices") (part "Res2"))
    )
    (comp (ref "R47")
      (value "47K")
      (footprint "PcbLib1:0805")
      (description "Resistor")
      (fields (field (name "PUBLISHER") "Altium Limited"))
      (libsource (lib "Miscellaneous Devices") (part "Res2"))
    )
    (comp (ref "R48")
      (value "47K")
      (footprint "PcbLib1:0805")
      (description "Resistor")
      (fields (field (name "PUBLISHER") "Altium Limited"))
      (libsource (lib "Miscellaneous Devices") (part "Res2"))
    )
    (comp (ref "R49")
      (value "47K")
      (footprint "PcbLib1:0805")
      (description "Resistor")
      (fields (field (name "PUBLISHER") "Altium Limited"))
      (libsource (lib "Miscellaneous Devices") (part "Res2"))
    )
    (comp (ref "R50")
      (value "47K")
      (footprint "PcbLib1:0805")
      (description "Resistor")
      (fields (field (name "PUBLISHER") "Altium Limited"))
      (libsource (lib "Miscellaneous Devices") (part "Res2"))
    )
    (comp (ref "R51")
      (value "47K")
      (footprint "PcbLib1:0805")
      (description "Resistor")
      (fields (field (name "PUBLISHER") "Altium Limited"))
      (libsource (lib "Miscellaneous Devices") (part "Res2"))
    )
    (comp (ref "R52")
      (value "47K")
      (footprint "PcbLib1:0805")
      (description "Resistor")
      (fields (field (name "PUBLISHER") "Altium Limited"))
      (libsource (lib "Miscellaneous Devices") (part "Res2"))
    )
    (comp (ref "R53")
      (value "47K")
      (footprint "PcbLib1:0805")
      (description "Resistor")
      (fields (field (name "PUBLISHER") "Altium Limited"))
      (libsource (lib "Miscellaneous Devices") (part "Res2"))
    )
    (comp (ref "R56")
      (value "10K")
      (footprint "PcbLib1:0805")
      (description "Resistor")
      (fields (field (name "Comment") "10k") (field (name "PUBLISHER") "Altium Limited"))
      (libsource (lib "Miscellaneous Devices") (part "Res2"))
    )
    (comp (ref "R57")
      (value "4.7K")
      (footprint "PcbLib1:0805")
      (description "Resistor")
      (fields (field (name "PUBLISHER") "Altium Limited"))
      (libsource (lib "") (part "Res2_2"))
    )
    (comp (ref "R59")
      (value "10K")
      (footprint "PcbLib1:0805")
      (description "Resistor")
      (fields (field (name "Comment") "10k") (field (name "PUBLISHER") "Altium Limited"))
      (libsource (lib "") (part "Res2_1"))
    )
    (comp (ref "R60")
      (value "10K")
      (footprint "PcbLib1:0805")
      (description "Resistor")
      (fields (field (name "Comment") "10k") (field (name "PUBLISHER") "Altium Limited"))
      (libsource (lib "") (part "Res2_1"))
    )
    (comp (ref "R61")
      (value "10K")
      (footprint "PcbLib1:0805")
      (description "Resistor")
      (fields (field (name "Comment") "10k") (field (name "PUBLISHER") "Altium Limited"))
      (libsource (lib "") (part "Res2_1"))
    )
    (comp (ref "R64")
      (value "10K")
      (footprint "PcbLib1:0805")
      (description "Resistor")
      (fields (field (name "Comment") "10k") (field (name "PUBLISHER") "Altium Limited"))
      (libsource (lib "Miscellaneous Devices") (part "Res2"))
    )
    (comp (ref "R65")
      (value "4.7K")
      (footprint "PcbLib1:0805")
      (description "Resistor")
      (fields (field (name "PUBLISHER") "Altium Limited"))
      (libsource (lib "") (part "Res2_2"))
    )
    (comp (ref "R69")
      (value "10K")
      (footprint "PcbLib1:0805")
      (description "Resistor")
      (fields (field (name "Comment") "10k") (field (name "PUBLISHER") "Altium Limited"))
      (libsource (lib "Miscellaneous Devices") (part "Res2"))
    )
    (comp (ref "R70")
      (value "4.7K")
      (footprint "PcbLib1:0805")
      (description "Resistor")
      (fields (field (name "PUBLISHER") "Altium Limited"))
      (libsource (lib "") (part "Res2_2"))
    )
    (comp (ref "R74")
      (value "10K")
      (footprint "PcbLib1:0805")
      (description "Resistor")
      (fields (field (name "Comment") "10k") (field (name "PUBLISHER") "Altium Limited"))
      (libsource (lib "Miscellaneous Devices") (part "Res2"))
    )
    (comp (ref "R75")
      (value "4.7K")
      (footprint "PcbLib1:0805")
      (description "Resistor")
      (fields (field (name "PUBLISHER") "Altium Limited"))
      (libsource (lib "") (part "Res2_2"))
    )
    (comp (ref "R79")
      (value "10K")
      (footprint "PcbLib1:0805")
      (description "Resistor")
      (fields (field (name "Comment") "10k") (field (name "PUBLISHER") "Altium Limited"))
      (libsource (lib "Miscellaneous Devices") (part "Res2"))
    )
    (comp (ref "R80")
      (value "4.7K")
      (footprint "PcbLib1:0805")
      (description "Resistor")
      (fields (field (name "PUBLISHER") "Altium Limited"))
      (libsource (lib "") (part "Res2_2"))
    )
    (comp (ref "R84")
      (value "10K")
      (footprint "PcbLib1:0805")
      (description "Resistor")
      (fields (field (name "Comment") "10k") (field (name "PUBLISHER") "Altium Limited"))
      (libsource (lib "Miscellaneous Devices") (part "Res2"))
    )
    (comp (ref "R85")
      (value "4.7K")
      (footprint "PcbLib1:0805")
      (description "Resistor")
      (fields (field (name "PUBLISHER") "Altium Limited"))
      (libsource (lib "") (part "Res2_2"))
    )
    (comp (ref "R87")
      (value "10K")
      (footprint "PcbLib1:0805")
      (description "Resistor")
      (fields (field (name "Comment") "10k") (field (name "PUBLISHER") "Altium Limited"))
      (libsource (lib "") (part "Res2_1"))
    )
    (comp (ref "R88")
      (value "10K")
      (footprint "PcbLib1:0805")
      (description "Resistor")
      (fields (field (name "Comment") "10k") (field (name "PUBLISHER") "Altium Limited"))
      (libsource (lib "") (part "Res2_1"))
    )
    (comp (ref "R89")
      (value "10K")
      (footprint "PcbLib1:0805")
      (description "Resistor")
      (fields (field (name "Comment") "10k") (field (name "PUBLISHER") "Altium Limited"))
      (libsource (lib "") (part "Res2_1"))
    )
    (comp (ref "R96")
      (value "10K")
      (footprint "PcbLib1:0805")
      (description "Resistor")
      (fields (field (name "Comment") "10k") (field (name "PUBLISHER") "Altium Limited"))
      (libsource (lib "Miscellaneous Devices") (part "Res2"))
    )
    (comp (ref "R97")
      (value "20")
      (footprint "PcbLib1:0805")
      (description "Resistor")
      (fields (field (name "PUBLISHER") "Altium Limited"))
      (libsource (lib "") (part "Res2_1"))
    )
    (comp (ref "R98")
      (value "120")
      (footprint "PcbLib1:0805")
      (description "Resistor")
      (fields (field (name "PUBLISHER") "Altium Limited"))
      (libsource (lib "") (part "Res2_3"))
    )
    (comp (ref "R100")
      (value "20")
      (footprint "PcbLib1:0805")
      (description "Resistor")
      (fields (field (name "PUBLISHER") "Altium Limited"))
      (libsource (lib "") (part "Res2_1"))
    )
    (comp (ref "TM1")
      (value "LM7824CT")
      (footprint "常用元件封装:TO-220")
      (libsource (lib "单片机及相关") (part "LM7824CT"))
    )
    (comp (ref "U1")
      (value "LM2575-5")
      (footprint "PcbLib1:D2PAK")
      (libsource (lib "ATmega169") (part "LM2575"))
    )
    (comp (ref "U2")
      (value "ULN2803")
      (footprint "PcbLib1:SOP-18_300mil")
      (libsource (lib "Schlib1") (part "ULN2803"))
    )
    (comp (ref "U3")
      (value "ATmega2560")
      (footprint "PcbLib1:TQFP100")
      (libsource (lib "Schlib1") (part "ATmega1280"))
    )
    (comp (ref "U4")
      (value "ULN2803")
      (footprint "PcbLib1:SOP-18_300mil")
      (libsource (lib "Schlib1") (part "ULN2803"))
    )
    (comp (ref "U5")
      (value "AMS1117-3.3_C166063")
      (footprint "PcbLib1:SOT-223_L6.7-W3.5-P2.30-BR")
      (fields
        (field (name "BOM_SUPPLIER PART") "C166063")
        (field (name "BOM_MANUFACTURER PART") "AMS1117-1.5")
        (field (name "CONTRIBUTOR") "LCSC")
      )
      (libsource (lib "Schlib1") (part "AMS1117-1.5_C166063"))
    )
    (comp (ref "U12")
      (value "TB6643KQ")
      (footprint "PcbLib1:TA8428 - S")
      (libsource (lib "") (part "Component_1_1"))
    )
    (comp (ref "U13")
      (value "TB6643KQ")
      (footprint "PcbLib1:TA8428 - S")
      (libsource (lib "") (part "Component_1_1"))
    )
    (comp (ref "U20")
      (value "DS1302")
      (footprint "PcbLib1:SOIC-8_150mil")
      (libsource (lib "单片机及相关") (part "DS1302"))
    )
    (comp (ref "U21")
      (value "AT24C02")
      (footprint "PcbLib1:SOIC-8_150mil")
      (libsource (lib "单片机及相关") (part "24CXX"))
    )
    (comp (ref "Y1")
      (value "X803832768KGD4GI")
      (footprint "PcbLib1:YSX306")
      (description "Crystal")
      (libsource (lib "Miscellaneous Devices") (part "CRYSTAL"))
    )
    (comp (ref "Y2")
      (value "14.7456MHZ")
      (footprint "PcbLib1:HC-49SMD")
      (description "Crystal")
      (libsource (lib "ATmega169_1") (part "CRYSTAL"))
    )
  )
  (nets
    (net (code "1") (name "+3.3V") (class "Default")
      (node (ref "C12") (pin "1") (pinfunction "1_1") (pintype "passive"))
      (node (ref "C9") (pin "1") (pintype "passive"))
      (node (ref "P17") (pin "8") (pinfunction "8_8") (pintype "passive"))
      (node (ref "U5") (pin "2") (pinfunction "Out_2") (pintype "passive"))
    )
    (net (code "2") (name "/485-EN") (class "Default")
      (node (ref "C29") (pin "2") (pinfunction "2_2") (pintype "passive"))
      (node (ref "IC1") (pin "2") (pinfunction "/RE_2") (pintype "passive"))
      (node (ref "IC1") (pin "3") (pinfunction "DE_3") (pintype "passive"))
      (node (ref "U3") (pin "65") (pinfunction "PJ2_65") (pintype "passive"))
    )
    (net (code "3") (name "/485-RXD") (class "Default")
      (node (ref "IC1") (pin "1") (pinfunction "RO_1") (pintype "passive"))
      (node (ref "P20") (pin "1") (pinfunction "1_1") (pintype "passive"))
      (node (ref "U3") (pin "63") (pinfunction "PJ0(RXD3)_63") (pintype "passive"))
    )
    (net (code "4") (name "/485-TXD") (class "Default")
      (node (ref "IC1") (pin "4") (pinfunction "DI_4") (pintype "passive"))
      (node (ref "P20") (pin "2") (pinfunction "2_2") (pintype "passive"))
      (node (ref "U3") (pin "64") (pinfunction "PJ1(TXD3)_64") (pintype "passive"))
    )
    (net (code "5") (name "/AC24L") (class "Default")
      (node (ref "DB1") (pin "1") (pinfunction "AC_1") (pintype "passive"))
      (node (ref "J3") (pin "4") (pinfunction "4_4") (pintype "passive"))
    )
    (net (code "6") (name "/AC24N") (class "Default")
      (node (ref "DB1") (pin "2") (pinfunction "AC_2") (pintype "passive"))
      (node (ref "J3") (pin "5") (pinfunction "5_5") (pintype "passive"))
    )
    (net (code "7") (name "/AC230_L") (class "Default")
      (node (ref "J1") (pin "1") (pinfunction "1_1") (pintype "passive"))
      (node (ref "J1") (pin "3") (pinfunction "3_3") (pintype "passive"))
      (node (ref "J3") (pin "1") (pinfunction "1_1") (pintype "passive"))
      (node (ref "J4") (pin "1") (pinfunction "1_1") (pintype "passive"))
    )
    (net (code "8") (name "/AC230_N") (class "Default")
      (node (ref "J3") (pin "2") (pinfunction "2_2") (pintype "passive"))
      (node (ref "J4") (pin "3") (pinfunction "3_3") (pintype "passive"))
      (node (ref "K1") (pin "1") (pinfunction "1_1") (pintype "passive"))
      (node (ref "K1") (pin "3") (pinfunction "3_3") (pintype "passive"))
      (node (ref "K7") (pin "1") (pinfunction "1_1") (pintype "passive"))
      (node (ref "K7") (pin "3") (pinfunction "3_3") (pintype "passive"))
    )
    (net (code "9") (name "/ACOUTA") (class "Default")
      (node (ref "J1") (pin "2") (pinfunction "2_2") (pintype "passive"))
      (node (ref "K1") (pin "2") (pinfunction "2_2") (pintype "passive"))
      (node (ref "K1") (pin "4") (pinfunction "4_4") (pintype "passive"))
    )
    (net (code "10") (name "/ACOUTB") (class "Default")
      (node (ref "J1") (pin "4") (pinfunction "4_4") (pintype "passive"))
      (node (ref "K7") (pin "2") (pinfunction "2_2") (pintype "passive"))
      (node (ref "K7") (pin "4") (pinfunction "4_4") (pintype "passive"))
    )
    (net (code "11") (name "/ADC_NTC") (class "Default")
      (node (ref "R28") (pin "1") (pinfunction "1_1") (pintype "passive"))
      (node (ref "R29") (pin "2") (pinfunction "2_2") (pintype "passive"))
      (node (ref "U3") (pin "84") (pinfunction "PK5(ADC13)_84") (pintype "passive"))
    )
    (net (code "12") (name "/AOT1") (class "Default")
      (node (ref "U2") (pin "1") (pinfunction "IN1_1") (pintype "passive"))
      (node (ref "U3") (pin "9") (pinfunction "PE7_9") (pintype "passive"))
    )
    (net (code "13") (name "/AOT2") (class "Default")
      (node (ref "U2") (pin "2") (pinfunction "IN2_2") (pintype "passive"))
      (node (ref "U3") (pin "8") (pinfunction "PE6_8") (pintype "passive"))
    )
    (net (code "14") (name "/AOT3") (class "Default")
      (node (ref "U2") (pin "3") (pinfunction "IN3_3") (pintype "passive"))
      (node (ref "U3") (pin "7") (pinfunction "PE5_7") (pintype "passive"))
    )
    (net (code "15") (name "/AOT4") (class "Default")
      (node (ref "U2") (pin "4") (pinfunction "IN4_4") (pintype "passive"))
      (node (ref "U3") (pin "6") (pinfunction "PE4_6") (pintype "passive"))
    )
    (net (code "16") (name "/AOT5") (class "Default")
      (node (ref "U2") (pin "5") (pinfunction "IN5_5") (pintype "passive"))
      (node (ref "U3") (pin "5") (pinfunction "PE3_5") (pintype "passive"))
    )
    (net (code "17") (name "/AOT6") (class "Default")
      (node (ref "U2") (pin "6") (pinfunction "IN6_6") (pintype "passive"))
      (node (ref "U3") (pin "4") (pinfunction "PE2_4") (pintype "passive"))
    )
    (net (code "18") (name "/AOT8") (class "Default")
      (node (ref "R40") (pin "1") (pinfunction "1_1") (pintype "passive"))
      (node (ref "U3") (pin "1") (pinfunction "PG5_1") (pintype "passive"))
    )
    (net (code "19") (name "/AREF") (class "Default")
      (node (ref "C24") (pin "2") (pinfunction "2_2") (pintype "passive"))
      (node (ref "U3") (pin "98") (pinfunction "AREF_98") (pintype "passive"))
    )
    (net (code "20") (name "/ASW_1") (class "Default")
      (node (ref "D2") (pin "2") (pinfunction "K_2") (pintype "passive"))
      (node (ref "K1") (pin "6") (pinfunction "6_6") (pintype "passive"))
      (node (ref "U2") (pin "14") (pinfunction "OT5_14") (pintype "passive"))
    )
    (net (code "21") (name "/ASW_2") (class "Default")
      (node (ref "D9") (pin "2") (pinfunction "K_2") (pintype "passive"))
      (node (ref "K7") (pin "6") (pinfunction "6_6") (pintype "passive"))
      (node (ref "U2") (pin "13") (pinfunction "OT6_13") (pintype "passive"))
    )
    (net (code "22") (name "/AVCC") (class "Default")
      (node (ref "L2") (pin "1") (pinfunction "1_1") (pintype "passive"))
      (node (ref "U3") (pin "100") (pinfunction "AVCC_100") (pintype "passive"))
    )
    (net (code "23") (name "/DATA_INA") (class "Default")
      (node (ref "P2") (pin "4") (pinfunction "Collector_4") (pintype "passive"))
      (node (ref "R12") (pin "2") (pinfunction "2_2") (pintype "passive"))
      (node (ref "U3") (pin "59") (pinfunction "PC6_59") (pintype "passive"))
    )
    (net (code "24") (name "/DATA_INB") (class "Default")
      (node (ref "P3") (pin "4") (pinfunction "Collector_4") (pintype "passive"))
      (node (ref "R14") (pin "2") (pinfunction "2_2") (pintype "passive"))
      (node (ref "U3") (pin "58") (pinfunction "PC5_58") (pintype "passive"))
    )
    (net (code "25") (name "/DATA_OUT") (class "Default")
      (node (ref "JP1") (pin "3") (pinfunction "3_3") (pintype "passive"))
      (node (ref "U4") (pin "11") (pinfunction "OT8_11") (pintype "passive"))
    )
    (net (code "26") (name "/EP_CLK") (class "Default")
      (node (ref "U21") (pin "6") (pinfunction "CLK_6") (pintype "passive"))
      (node (ref "U3") (pin "51") (pinfunction "PG0_51") (pintype "passive"))
    )
    (net (code "27") (name "/EP_DIO") (class "Default")
      (node (ref "U21") (pin "5") (pinfunction "DATA_5") (pintype "passive"))
      (node (ref "U3") (pin "52") (pinfunction "PG1_52") (pintype "passive"))
    )
    (net (code "28") (name "/EP_STB") (class "Default")
      (node (ref "U21") (pin "7") (pinfunction "HOLD_7") (pintype "passive"))
      (node (ref "U3") (pin "50") (pinfunction "PD7_50") (pintype "passive"))
    )
    (net (code "29") (name "/IN1A") (class "Default")
      (node (ref "R31") (pin "1") (pinfunction "1_1") (pintype "passive"))
      (node (ref "U13") (pin "1") (pinfunction "INA_1") (pintype "passive"))
      (node (ref "U3") (pin "75") (pinfunction "PA3_75") (pintype "passive"))
    )
    (net (code "30") (name "/IN1B") (class "Default")
      (node (ref "R32") (pin "1") (pinfunction "1_1") (pintype "passive"))
      (node (ref "U13") (pin "2") (pinfunction "INB_2") (pintype "passive"))
      (node (ref "U3") (pin "74") (pinfunction "PA4_74") (pintype "passive"))
    )
    (net (code "31") (name "/IN2A") (class "Default")
      (node (ref "R34") (pin "1") (pinfunction "1_1") (pintype "passive"))
      (node (ref "U12") (pin "1") (pinfunction "INA_1") (pintype "passive"))
      (node (ref "U3") (pin "73") (pinfunction "PA5_73") (pintype "passive"))
    )
    (net (code "32") (name "/IN2B") (class "Default")
      (node (ref "R33") (pin "1") (pinfunction "1_1") (pintype "passive"))
      (node (ref "U12") (pin "2") (pinfunction "INB_2") (pintype "passive"))
      (node (ref "U3") (pin "72") (pinfunction "PA6_72") (pintype "passive"))
    )
    (net (code "33") (name "/LIN_B1") (class "Default")
      (node (ref "P5") (pin "4") (pinfunction "Collector_4") (pintype "passive"))
      (node (ref "R5") (pin "1") (pinfunction "1_1") (pintype "passive"))
      (node (ref "U3") (pin "12") (pinfunction "PH0(RXD2)_12") (pintype "passive"))
    )
    (net (code "34") (name "/LIN_B2") (class "Default")
      (node (ref "P6") (pin "4") (pinfunction "Collector_4") (pintype "passive"))
      (node (ref "R3") (pin "1") (pinfunction "1_1") (pintype "passive"))
      (node (ref "U3") (pin "13") (pinfunction "PH1(TXD2)_13") (pintype "passive"))
    )
    (net (code "35") (name "/LIN_B3") (class "Default")
      (node (ref "P7") (pin "4") (pinfunction "Collector_4") (pintype "passive"))
      (node (ref "R36") (pin "1") (pinfunction "1_1") (pintype "passive"))
      (node (ref "U3") (pin "14") (pinfunction "PH2_14") (pintype "passive"))
    )
    (net (code "36") (name "/LIN_B4") (class "Default")
      (node (ref "P8") (pin "4") (pinfunction "Collector_4") (pintype "passive"))
      (node (ref "R41") (pin "1") (pinfunction "1_1") (pintype "passive"))
      (node (ref "U3") (pin "15") (pinfunction "PH3_15") (pintype "passive"))
    )
    (net (code "37") (name "/LIN_B5") (class "Default")
      (node (ref "P9") (pin "4") (pinfunction "Collector_4") (pintype "passive"))
      (node (ref "R56") (pin "1") (pinfunction "1_1") (pintype "passive"))
      (node (ref "U3") (pin "16") (pinfunction "PH4_16") (pintype "passive"))
    )
    (net (code "38") (name "/LROUT5") (class "Default")
      (node (ref "U3") (pin "69") (pinfunction "PJ6_69") (pintype "passive"))
      (node (ref "U4") (pin "5") (pinfunction "IN5_5") (pintype "passive"))
    )
    (net (code "39") (name "/LROUT6") (class "Default")
      (node (ref "U3") (pin "68") (pinfunction "PJ5_68") (pintype "passive"))
      (node (ref "U4") (pin "6") (pinfunction "IN6_6") (pintype "passive"))
    )
    (net (code "40") (name "/LROUT7") (class "Default")
      (node (ref "U3") (pin "67") (pinfunction "PJ4_67") (pintype "passive"))
      (node (ref "U4") (pin "7") (pinfunction "IN7_7") (pintype "passive"))
    )
    (net (code "41") (name "/LROUT8") (class "Default")
      (node (ref "U3") (pin "66") (pinfunction "PJ3_66") (pintype "passive"))
      (node (ref "U4") (pin "8") (pinfunction "IN8_8") (pintype "passive"))
    )
    (net (code "42") (name "/LSW_A1") (class "Default")
      (node (ref "D13") (pin "2") (pinfunction "K_2") (pintype "passive"))
      (node (ref "K9") (pin "6") (pinfunction "6_6") (pintype "passive"))
      (node (ref "U2") (pin "15") (pinfunction "OT4_15") (pintype "passive"))
    )
    (net (code "43") (name "/LSW_A2") (class "Default")
      (node (ref "D14") (pin "2") (pinfunction "K_2") (pintype "passive"))
      (node (ref "K10") (pin "6") (pinfunction "6_6") (pintype "passive"))
      (node (ref "U2") (pin "16") (pinfunction "OT3_16") (pintype "power_in"))
    )
    (net (code "44") (name "/LSW_A3") (class "Default")
      (node (ref "D15") (pin "2") (pinfunction "K_2") (pintype "passive"))
      (node (ref "K11") (pin "6") (pinfunction "6_6") (pintype "passive"))
      (node (ref "U2") (pin "17") (pinfunction "OT2_17") (pintype "passive"))
    )
    (net (code "45") (name "/L_TER") (class "Default")
      (node (ref "C8") (pin "2") (pinfunction "2_2") (pintype "passive"))
      (node (ref "P15") (pin "2") (pinfunction "2_2") (pintype "passive"))
      (node (ref "R16") (pin "2") (pinfunction "2_2") (pintype "passive"))
      (node (ref "R17") (pin "2") (pinfunction "2_2") (pintype "passive"))
      (node (ref "R18") (pin "2") (pinfunction "2_2") (pintype "passive"))
      (node (ref "R19") (pin "2") (pinfunction "2_2") (pintype "passive"))
      (node (ref "R20") (pin "2") (pinfunction "2_2") (pintype "passive"))
      (node (ref "R22") (pin "2") (pinfunction "2_2") (pintype "passive"))
      (node (ref "R24") (pin "2") (pinfunction "2_2") (pintype "passive"))
      (node (ref "R25") (pin "2") (pinfunction "2_2") (pintype "passive"))
      (node (ref "R7") (pin "2") (pinfunction "2_2") (pintype "passive"))
      (node (ref "R9") (pin "2") (pinfunction "2_2") (pintype "passive"))
      (node (ref "U3") (pin "83") (pinfunction "PK6(ADC14)_83") (pintype "passive"))
    )
    (net (code "46") (name "/MD1_A") (class "Default")
      (node (ref "J5") (pin "1") (pinfunction "1_1") (pintype "passive"))
      (node (ref "R11") (pin "1") (pinfunction "1_1") (pintype "passive"))
      (node (ref "U13") (pin "3") (pinfunction "OUTA_3") (pintype "passive"))
    )
    (net (code "47") (name "/MD1_B") (class "Default")
      (node (ref "C17") (pin "2") (pinfunction "2_2") (pintype "passive"))
      (node (ref "J5") (pin "2") (pinfunction "2_2") (pintype "passive"))
      (node (ref "U13") (pin "5") (pinfunction "OUTB_5") (pintype "passive"))
    )
    (net (code "48") (name "/MD2_A") (class "Default")
      (node (ref "J5") (pin "3") (pinfunction "3_3") (pintype "passive"))
      (node (ref "R10") (pin "1") (pinfunction "1_1") (pintype "passive"))
      (node (ref "U12") (pin "3") (pinfunction "OUTA_3") (pintype "passive"))
    )
    (net (code "49") (name "/MD2_B") (class "Default")
      (node (ref "C16") (pin "2") (pinfunction "2_2") (pintype "passive"))
      (node (ref "J5") (pin "4") (pinfunction "4_4") (pintype "passive"))
      (node (ref "U12") (pin "5") (pinfunction "OUTB_5") (pintype "passive"))
    )
    (net (code "50") (name "/MD_DC12V") (class "Default")
      (node (ref "C18") (pin "1") (pinfunction "1_1") (pintype "passive"))
      (node (ref "P1") (pin "2") (pinfunction "2_2") (pintype "passive"))
      (node (ref "U12") (pin "7") (pinfunction "VCC_7") (pintype "passive"))
      (node (ref "U13") (pin "7") (pinfunction "VCC_7") (pintype "passive"))
    )
    (net (code "51") (name "/RESET") (class "Default")
      (node (ref "C32") (pin "2") (pinfunction "2_2") (pintype "passive"))
      (node (ref "D19") (pin "1") (pinfunction "A_1") (pintype "passive"))
      (node (ref "JP5") (pin "5") (pinfunction "5_5") (pintype "passive"))
      (node (ref "R96") (pin "1") (pinfunction "1_1") (pintype "passive"))
      (node (ref "U3") (pin "30") (pinfunction "RESET_30") (pintype "passive"))
    )
    (net (code "52") (name "/RIN_B1") (class "Default")
      (node (ref "P10") (pin "4") (pinfunction "Collector_4") (pintype "passive"))
      (node (ref "R64") (pin "1") (pinfunction "1_1") (pintype "passive"))
      (node (ref "U3") (pin "57") (pinfunction "PC4_57") (pintype "passive"))
    )
    (net (code "53") (name "/RIN_B2") (class "Default")
      (node (ref "P11") (pin "4") (pinfunction "Collector_4") (pintype "passive"))
      (node (ref "R69") (pin "1") (pinfunction "1_1") (pintype "passive"))
      (node (ref "U3") (pin "56") (pinfunction "PC3_56") (pintype "passive"))
    )
    (net (code "54") (name "/RIN_B3") (class "Default")
      (node (ref "P12") (pin "4") (pinfunction "Collector_4") (pintype "passive"))
      (node (ref "R74") (pin "1") (pinfunction "1_1") (pintype "passive"))
      (node (ref "U3") (pin "55") (pinfunction "PC2_55") (pintype "passive"))
    )
    (net (code "55") (name "/RIN_B4") (class "Default")
      (node (ref "P13") (pin "4") (pinfunction "Collector_4") (pintype "passive"))
      (node (ref "R79") (pin "1") (pinfunction "1_1") (pintype "passive"))
      (node (ref "U3") (pin "54") (pinfunction "PC1_54") (pintype "passive"))
    )
    (net (code "56") (name "/RIN_B5") (class "Default")
      (node (ref "P14") (pin "4") (pinfunction "Collector_4") (pintype "passive"))
      (node (ref "R84") (pin "1") (pinfunction "1_1") (pintype "passive"))
      (node (ref "U3") (pin "53") (pinfunction "PC0_53") (pintype "passive"))
    )
    (net (code "57") (name "/RSW_A1") (class "Default")
      (node (ref "D16") (pin "2") (pinfunction "K_2") (pintype "passive"))
      (node (ref "K12") (pin "6") (pinfunction "6_6") (pintype "passive"))
      (node (ref "U4") (pin "12") (pinfunction "OT7_12") (pintype "passive"))
    )
    (net (code "58") (name "/RSW_A2") (class "Default")
      (node (ref "D17") (pin "2") (pinfunction "K_2") (pintype "passive"))
      (node (ref "K13") (pin "6") (pinfunction "6_6") (pintype "passive"))
      (node (ref "U4") (pin "13") (pinfunction "OT6_13") (pintype "passive"))
    )
    (net (code "59") (name "/RSW_A3") (class "Default")
      (node (ref "D18") (pin "2") (pinfunction "K_2") (pintype "passive"))
      (node (ref "K14") (pin "6") (pinfunction "6_6") (pintype "passive"))
      (node (ref "U4") (pin "14") (pinfunction "OT5_14") (pintype "passive"))
    )
    (net (code "60") (name "/RXD0") (class "Default")
      (node (ref "P17") (pin "2") (pinfunction "2_2") (pintype "passive"))
      (node (ref "U3") (pin "2") (pinfunction "PE0(RXD0)_2") (pintype "passive"))
    )
    (net (code "61") (name "/RXD1") (class "Default")
      (node (ref "R39") (pin "2") (pinfunction "2_2") (pintype "passive"))
      (node (ref "U3") (pin "45") (pinfunction "PD2(RXD1)_45") (pintype "passive"))
    )
    (net (code "62") (name "/R_CLK") (class "Default")
      (node (ref "U20") (pin "7") (pinfunction "SCLK_7") (pintype "passive"))
      (node (ref "U3") (pin "17") (pinfunction "PH5_17") (pintype "passive"))
    )
    (net (code "63") (name "/R_DIO") (class "Default")
      (node (ref "U20") (pin "6") (pinfunction "I/O_6") (pintype "bidirectional"))
      (node (ref "U3") (pin "18") (pinfunction "PH6_18") (pintype "passive"))
    )
    (net (code "64") (name "/R_STB") (class "Default")
      (node (ref "U20") (pin "5") (pinfunction "RST_5") (pintype "passive"))
      (node (ref "U3") (pin "19") (pinfunction "PB0_19") (pintype "passive"))
    )
    (net (code "65") (name "/R_TER") (class "Default")
      (node (ref "C11") (pin "2") (pinfunction "2_2") (pintype "passive"))
      (node (ref "P16") (pin "1") (pinfunction "1_1") (pintype "passive"))
      (node (ref "R44") (pin "2") (pinfunction "2_2") (pintype "passive"))
      (node (ref "R45") (pin "2") (pinfunction "2_2") (pintype "passive"))
      (node (ref "R46") (pin "2") (pinfunction "2_2") (pintype "passive"))
      (node (ref "R47") (pin "2") (pinfunction "2_2") (pintype "passive"))
      (node (ref "R48") (pin "2") (pinfunction "2_2") (pintype "passive"))
      (node (ref "R49") (pin "2") (pinfunction "2_2") (pintype "passive"))
      (node (ref "R50") (pin "2") (pinfunction "2_2") (pintype "passive"))
      (node (ref "R51") (pin "2") (pinfunction "2_2") (pintype "passive"))
      (node (ref "R52") (pin "2") (pinfunction "2_2") (pintype "passive"))
      (node (ref "R53") (pin "2") (pinfunction "2_2") (pintype "passive"))
      (node (ref "U3") (pin "82") (pinfunction "PK7(ADC15)_82") (pintype "passive"))
    )
    (net (code "66") (name "/SPI_MISO") (class "Default")
      (node (ref "JP5") (pin "9") (pinfunction "9_9") (pintype "passive"))
      (node (ref "U3") (pin "22") (pinfunction "PB3_22") (pintype "passive"))
    )
    (net (code "67") (name "/SPI_MOSI") (class "Default")
      (node (ref "JP5") (pin "1") (pinfunction "1_1") (pintype "passive"))
      (node (ref "U3") (pin "21") (pinfunction "PB2_21") (pintype "passive"))
    )
    (net (code "68") (name "/SPI_SCK") (class "Default")
      (node (ref "JP5") (pin "7") (pinfunction "7_7") (pintype "passive"))
      (node (ref "U3") (pin "20") (pinfunction "PB1_20") (pintype "passive"))
    )
    (net (code "69") (name "/TXD0") (class "Default")
      (node (ref "P17") (pin "4") (pinfunction "4_4") (pintype "passive"))
      (node (ref "U3") (pin "3") (pinfunction "PE1(TXD0)_3") (pintype "passive"))
    )
    (net (code "70") (name "/TXD1") (class "Default")
      (node (ref "R37") (pin "2") (pinfunction "2_2") (pintype "passive"))
      (node (ref "U3") (pin "46") (pinfunction "PD3(TXD1)_46") (pintype "passive"))
    )
    (net (code "71") (name "/W_DC24V") (class "Default")
      (node (ref "C5") (pin "1") (pinfunction "1_1") (pintype "passive"))
      (node (ref "JP1") (pin "4") (pinfunction "4_4") (pintype "passive"))
    )
    (net (code "72") (name "/W_GND") (class "Default")
      (node (ref "C5") (pin "2") (pinfunction "2_2") (pintype "passive"))
      (node (ref "JP1") (pin "1") (pinfunction "1_1") (pintype "passive"))
    )
    (net (code "73") (name "/XTAL1") (class "Default")
      (node (ref "C31") (pin "2") (pinfunction "2_2") (pintype "passive"))
      (node (ref "U3") (pin "34") (pinfunction "XTAL1_34") (pintype "passive"))
      (node (ref "Y2") (pin "2") (pinfunction "2_2") (pintype "passive"))
    )
    (net (code "74") (name "/XTAL2") (class "Default")
      (node (ref "C30") (pin "2") (pinfunction "2_2") (pintype "passive"))
      (node (ref "U3") (pin "33") (pinfunction "XTAL2_33") (pintype "passive"))
      (node (ref "Y2") (pin "1") (pinfunction "1_1") (pintype "passive"))
    )
    (net (code "75") (name "/X_ASTB") (class "Default")
      (node (ref "JP3") (pin "3") (pinfunction "3_3") (pintype "passive"))
      (node (ref "U3") (pin "47") (pinfunction "PD4_47") (pintype "passive"))
    )
    (net (code "76") (name "/X_BSTB") (class "Default")
      (node (ref "JP3") (pin "4") (pinfunction "4_4") (pintype "passive"))
      (node (ref "U3") (pin "44") (pinfunction "PD1_44") (pintype "passive"))
    )
    (net (code "77") (name "/X_CLK") (class "Default")
      (node (ref "JP3") (pin "2") (pinfunction "2_2") (pintype "passive"))
      (node (ref "U3") (pin "48") (pinfunction "PD5_48") (pintype "passive"))
    )
    (net (code "78") (name "/X_CSTB") (class "Default")
      (node (ref "JP3") (pin "5") (pinfunction "5_5") (pintype "passive"))
      (node (ref "U3") (pin "43") (pinfunction "PD0_43") (pintype "passive"))
    )
    (net (code "79") (name "/X_DIO") (class "Default")
      (node (ref "JP3") (pin "1") (pinfunction "1_1") (pintype "passive"))
      (node (ref "U3") (pin "49") (pinfunction "PD6_49") (pintype "passive"))
    )
    (net (code "80") (name "/X_DSTB") (class "Default")
      (node (ref "JP3") (pin "6") (pinfunction "6_6") (pintype "passive"))
      (node (ref "U3") (pin "42") (pinfunction "PL7_42") (pintype "passive"))
    )
    (net (code "81") (name "/X_ESTB") (class "Default")
      (node (ref "JP3") (pin "7") (pinfunction "7_7") (pintype "passive"))
      (node (ref "U3") (pin "41") (pinfunction "PL6_41") (pintype "passive"))
    )
    (net (code "82") (name "/X_FSTB") (class "Default")
      (node (ref "JP3") (pin "8") (pinfunction "8_8") (pintype "passive"))
      (node (ref "U3") (pin "40") (pinfunction "PL5_40") (pintype "passive"))
    )
    (net (code "83") (name "/X_GSTB") (class "Default")
      (node (ref "JP3") (pin "9") (pinfunction "9_9") (pintype "passive"))
      (node (ref "U3") (pin "39") (pinfunction "PL4_39") (pintype "passive"))
    )
    (net (code "84") (name "/X_SW_1") (class "Default")
      (node (ref "JP3") (pin "10") (pinfunction "10_10") (pintype "passive"))
      (node (ref "U3") (pin "38") (pinfunction "PL3_38") (pintype "passive"))
    )
    (net (code "85") (name "/X_SW_2") (class "Default")
      (node (ref "JP3") (pin "11") (pinfunction "11_11") (pintype "passive"))
      (node (ref "U3") (pin "37") (pinfunction "PL2_37") (pintype "passive"))
    )
    (net (code "86") (name "/X_SW_3") (class "Default")
      (node (ref "JP3") (pin "12") (pinfunction "12_12") (pintype "passive"))
      (node (ref "U3") (pin "36") (pinfunction "PL1_36") (pintype "passive"))
    )
    (net (code "87") (name "/X_SW_4") (class "Default")
      (node (ref "JP3") (pin "13") (pinfunction "13_13") (pintype "passive"))
      (node (ref "U3") (pin "35") (pinfunction "PL0_35") (pintype "passive"))
    )
    (net (code "88") (name "DC24V") (class "Default")
      (node (ref "C14") (pin "1") (pinfunction "1_1") (pintype "passive"))
      (node (ref "C15") (pin "2") (pinfunction "2_2") (pintype "passive"))
      (node (ref "C4") (pin "1") (pinfunction "1_1") (pintype "passive"))
      (node (ref "C6") (pin "1") (pinfunction "1_1") (pintype "passive"))
      (node (ref "C7") (pin "2") (pinfunction "2_2") (pintype "passive"))
      (node (ref "D3") (pin "2") (pinfunction "K_2") (pintype "passive"))
      (node (ref "J6") (pin "1") (pinfunction "1_1") (pintype "passive"))
      (node (ref "J7") (pin "1") (pinfunction "1_1") (pintype "passive"))
      (node (ref "K1") (pin "5") (pinfunction "5_5") (pintype "passive"))
      (node (ref "K10") (pin "5") (pinfunction "5_5") (pintype "passive"))
      (node (ref "K11") (pin "5") (pinfunction "5_5") (pintype "passive"))
      (node (ref "K12") (pin "5") (pinfunction "5_5") (pintype "passive"))
      (node (ref "K13") (pin "5") (pinfunction "5_5") (pintype "passive"))
      (node (ref "K14") (pin "5") (pinfunction "5_5") (pintype "passive"))
      (node (ref "K7") (pin "5") (pinfunction "5_5") (pintype "passive"))
      (node (ref "K9") (pin "5") (pinfunction "5_5") (pintype "passive"))
      (node (ref "P4") (pin "1") (pinfunction "1_1") (pintype "passive"))
      (node (ref "R2") (pin "2") (pinfunction "2_2") (pintype "passive"))
      (node (ref "R38") (pin "2") (pinfunction "2_2") (pintype "passive"))
      (node (ref "R59") (pin "2") (pinfunction "2_2") (pintype "passive"))
      (node (ref "R60") (pin "2") (pinfunction "2_2") (pintype "passive"))
      (node (ref "R61") (pin "2") (pinfunction "2_2") (pintype "passive"))
      (node (ref "R8") (pin "2") (pinfunction "2_2") (pintype "passive"))
      (node (ref "R87") (pin "2") (pinfunction "2_2") (pintype "passive"))
      (node (ref "R88") (pin "2") (pinfunction "2_2") (pintype "passive"))
      (node (ref "R89") (pin "2") (pinfunction "2_2") (pintype "passive"))
      (node (ref "TM1") (pin "3") (pinfunction "+24V_3") (pintype "passive"))
      (node (ref "U2") (pin "10") (pinfunction "COM_10") (pintype "passive"))
      (node (ref "U4") (pin "10") (pinfunction "COM_10") (pintype "passive"))
    )
    (net (code "89") (name "E+3.3V") (class "Default")
      (node (ref "M1") (pin "8") (pinfunction "VCC_8") (pintype "passive"))
      (node (ref "P17") (pin "7") (pinfunction "7_7") (pintype "passive"))
      (node (ref "R21") (pin "2") (pinfunction "2_2") (pintype "passive"))
      (node (ref "R23") (pin "2") (pinfunction "2_2") (pintype "passive"))
      (node (ref "R26") (pin "1") (pinfunction "1_1") (pintype "passive"))
    )
    (net (code "90") (name "EGND") (class "Default")
      (node (ref "M1") (pin "0") (pinfunction "GND_0") (pintype "passive"))
      (node (ref "M1") (pin "10") (pinfunction "GPIO15_10") (pintype "passive"))
      (node (ref "M1") (pin "9") (pinfunction "GND_9") (pintype "passive"))
      (node (ref "P17") (pin "5") (pinfunction "5_5") (pintype "passive"))
      (node (ref "P18") (pin "2") (pinfunction "2_2") (pintype "passive"))
    )
    (net (code "91") (name "GND") (class "Default")
      (node (ref "BT1") (pin "2") (pinfunction "-_2") (pintype "passive"))
      (node (ref "C1") (pin "1") (pinfunction "1_1") (pintype "passive"))
      (node (ref "C10") (pin "2") (pinfunction "2_2") (pintype "passive"))
      (node (ref "C11") (pin "1") (pinfunction "1_1") (pintype "passive"))
      (node (ref "C12") (pin "2") (pinfunction "2_2") (pintype "passive"))
      (node (ref "C14") (pin "2") (pinfunction "2_2") (pintype "passive"))
      (node (ref "C15") (pin "1") (pinfunction "1_1") (pintype "passive"))
      (node (ref "C18") (pin "2") (pinfunction "2_2") (pintype "passive"))
      (node (ref "C2") (pin "2") (pinfunction "2_2") (pintype "passive"))
      (node (ref "C20") (pin "1") (pinfunction "1_1") (pintype "passive"))
      (node (ref "C21") (pin "1") (pinfunction "1_1") (pintype "passive"))
      (node (ref "C22") (pin "1") (pinfunction "1_1") (pintype "passive"))
      (node (ref "C23") (pin "1") (pinfunction "1_1") (pintype "passive"))
      (node (ref "C24") (pin "1") (pinfunction "1_1") (pintype "passive"))
      (node (ref "C25") (pin "2") (pinfunction "2_2") (pintype "passive"))
      (node (ref "C26") (pin "2") (pinfunction "2_2") (pintype "passive"))
      (node (ref "C27") (pin "1") (pinfunction "1_1") (pintype "passive"))
      (node (ref "C28") (pin "1") (pinfunction "1_1") (pintype "passive"))
      (node (ref "C29") (pin "1") (pinfunction "1_1") (pintype "passive"))
      (node (ref "C3") (pin "2") (pinfunction "2_2") (pintype "passive"))
      (node (ref "C30") (pin "1") (pinfunction "1_1") (pintype "passive"))
      (node (ref "C31") (pin "1") (pinfunction "1_1") (pintype "passive"))
      (node (ref "C32") (pin "1") (pinfunction "1_1") (pintype "passive"))
      (node (ref "C34") (pin "2") (pinfunction "2_2") (pintype "passive"))
      (node (ref "C4") (pin "2") (pinfunction "2_2") (pintype "passive"))
      (node (ref "C6") (pin "2") (pinfunction "2_2") (pintype "passive"))
      (node (ref "C7") (pin "1") (pinfunction "1_1") (pintype "passive"))
      (node (ref "C8") (pin "1") (pinfunction "1_1") (pintype "passive"))
      (node (ref "C9") (pin "2") (pintype "passive"))
      (node (ref "D1") (pin "2") (pinfunction "K_2") (pintype "passive"))
      (node (ref "D4") (pin "1") (pinfunction "A_1") (pintype "passive"))
      (node (ref "DB1") (pin "4") (pinfunction "V-_4") (pintype "passive"))
      (node (ref "IC1") (pin "5") (pinfunction "GND_5") (pintype "passive"))
      (node (ref "J6") (pin "14") (pinfunction "14_14") (pintype "passive"))
      (node (ref "J6") (pin "3") (pinfunction "3_3") (pintype "passive"))
      (node (ref "J6") (pin "9") (pinfunction "9_9") (pintype "passive"))
      (node (ref "J7") (pin "14") (pinfunction "14_14") (pintype "passive"))
      (node (ref "J7") (pin "3") (pinfunction "3_3") (pintype "passive"))
      (node (ref "J7") (pin "9") (pinfunction "9_9") (pintype "passive"))
      (node (ref "JP1") (pin "2") (pinfunction "2_2") (pintype "passive"))
      (node (ref "JP3") (pin "14") (pinfunction "14_14") (pintype "passive"))
      (node (ref "JP3") (pin "15") (pinfunction "15_15") (pintype "passive"))
      (node (ref "JP3") (pin "16") (pinfunction "16_16") (pintype "passive"))
      (node (ref "JP3") (pin "17") (pinfunction "17_17") (pintype "passive"))
      (node (ref "JP4") (pin "1") (pinfunction "1_1") (pintype "passive"))
      (node (ref "JP5") (pin "10") (pinfunction "10_10") (pintype "passive"))
      (node (ref "JP6") (pin "1") (pinfunction "1_1") (pintype "passive"))
      (node (ref "P1") (pin "1") (pinfunction "1_1") (pintype "passive"))
      (node (ref "P10") (pin "2") (pinfunction "LED_Cathode_2") (pintype "passive"))
      (node (ref "P10") (pin "3") (pinfunction "Emitter_3") (pintype "passive"))
      (node (ref "P11") (pin "2") (pinfunction "LED_Cathode_2") (pintype "passive"))
      (node (ref "P11") (pin "3") (pinfunction "Emitter_3") (pintype "passive"))
      (node (ref "P12") (pin "2") (pinfunction "LED_Cathode_2") (pintype "passive"))
      (node (ref "P12") (pin "3") (pinfunction "Emitter_3") (pintype "passive"))
      (node (ref "P13") (pin "2") (pinfunction "LED_Cathode_2") (pintype "passive"))
      (node (ref "P13") (pin "3") (pinfunction "Emitter_3") (pintype "passive"))
      (node (ref "P14") (pin "2") (pinfunction "LED_Cathode_2") (pintype "passive"))
      (node (ref "P14") (pin "3") (pinfunction "Emitter_3") (pintype "passive"))
      (node (ref "P17") (pin "6") (pinfunction "6_6") (pintype "passive"))
      (node (ref "P19") (pin "3") (pinfunction "3_3") (pintype "passive"))
      (node (ref "P2") (pin "3") (pinfunction "Emitter_3") (pintype "passive"))
      (node (ref "P20") (pin "3") (pinfunction "3_3") (pintype "passive"))
      (node (ref "P3") (pin "3") (pinfunction "Emitter_3") (pintype "passive"))
      (node (ref "P5") (pin "2") (pinfunction "LED_Cathode_2") (pintype "passive"))
      (node (ref "P5") (pin "3") (pinfunction "Emitter_3") (pintype "passive"))
      (node (ref "P6") (pin "2") (pinfunction "LED_Cathode_2") (pintype "passive"))
      (node (ref "P6") (pin "3") (pinfunction "Emitter_3") (pintype "passive"))
      (node (ref "P7") (pin "2") (pinfunction "LED_Cathode_2") (pintype "passive"))
      (node (ref "P7") (pin "3") (pinfunction "Emitter_3") (pintype "passive"))
      (node (ref "P8") (pin "2") (pinfunction "LED_Cathode_2") (pintype "passive"))
      (node (ref "P8") (pin "3") (pinfunction "Emitter_3") (pintype "passive"))
      (node (ref "P9") (pin "2") (pinfunction "LED_Cathode_2") (pintype "passive"))
      (node (ref "P9") (pin "3") (pinfunction "Emitter_3") (pintype "passive"))
      (node (ref "Q1") (pin "E") (pintype "passive"))
      (node (ref "R16") (pin "1") (pinfunction "1_1") (pintype "passive"))
      (node (ref "R17") (pin "1") (pinfunction "1_1") (pintype "passive"))
      (node (ref "R18") (pin "1") (pinfunction "1_1") (pintype "passive"))
      (node (ref "R19") (pin "1") (pinfunction "1_1") (pintype "passive"))
      (node (ref "R20") (pin "1") (pinfunction "1_1") (pintype "passive"))
      (node (ref "R22") (pin "1") (pinfunction "1_1") (pintype "passive"))
      (node (ref "R24") (pin "1") (pinfunction "1_1") (pintype "passive"))
      (node (ref "R25") (pin "1") (pinfunction "1_1") (pintype "passive"))
      (node (ref "R29") (pin "1") (pinfunction "1_1") (pintype "passive"))
      (node (ref "R43") (pin "1") (pinfunction "1_1") (pintype "passive"))
      (node (ref "R44") (pin "1") (pinfunction "1_1") (pintype "passive"))
      (node (ref "R45") (pin "1") (pinfunction "1_1") (pintype "passive"))
      (node (ref "R46") (pin "1") (pinfunction "1_1") (pintype "passive"))
      (node (ref "R47") (pin "1") (pinfunction "1_1") (pintype "passive"))
      (node (ref "R48") (pin "1") (pinfunction "1_1") (pintype "passive"))
      (node (ref "R49") (pin "1") (pinfunction "1_1") (pintype "passive"))
      (node (ref "R50") (pin "1") (pinfunction "1_1") (pintype "passive"))
      (node (ref "R51") (pin "1") (pinfunction "1_1") (pintype "passive"))
      (node (ref "R52") (pin "1") (pinfunction "1_1") (pintype "passive"))
      (node (ref "R53") (pin "1") (pinfunction "1_1") (pintype "passive"))
      (node (ref "R7") (pin "1") (pinfunction "1_1") (pintype "passive"))
      (node (ref "R9") (pin "1") (pinfunction "1_1") (pintype "passive"))
      (node (ref "TM1") (pin "2") (pinfunction "Gnd_2") (pintype "passive"))
      (node (ref "U1") (pin "3") (pinfunction "GND_3") (pintype "passive"))
      (node (ref "U1") (pin "5") (pinfunction "ON/~{OFF}_5") (pintype "passive"))
      (node (ref "U12") (pin "4") (pinfunction "GND_4") (pintype "passive"))
      (node (ref "U13") (pin "4") (pinfunction "GND_4") (pintype "passive"))
      (node (ref "U2") (pin "9") (pinfunction "GND_9") (pintype "power_in"))
      (node (ref "U20") (pin "4") (pinfunction "GND_4") (pintype "passive"))
      (node (ref "U21") (pin "1") (pinfunction "A0_1") (pintype "passive"))
      (node (ref "U21") (pin "2") (pinfunction "A1_2") (pintype "passive"))
      (node (ref "U21") (pin "3") (pinfunction "A2_3") (pintype "passive"))
      (node (ref "U21") (pin "4") (pinfunction "GND_4") (pintype "passive"))
      (node (ref "U3") (pin "11") (pinfunction "GND_11") (pintype "passive"))
      (node (ref "U3") (pin "32") (pinfunction "GND_32") (pintype "passive"))
      (node (ref "U3") (pin "62") (pinfunction "GND_62") (pintype "passive"))
      (node (ref "U3") (pin "81") (pinfunction "GND_81") (pintype "passive"))
      (node (ref "U3") (pin "99") (pinfunction "GND_99") (pintype "passive"))
      (node (ref "U4") (pin "9") (pinfunction "GND_9") (pintype "power_in"))
      (node (ref "U5") (pin "1") (pinfunction "GND_1") (pintype "passive"))
    )
    (net (code "92") (name "Net-(BT1-+)") (class "Default")
      (node (ref "BT1") (pin "1") (pinfunction "+_1") (pintype "passive"))
      (node (ref "U20") (pin "8") (pinfunction "Vcc_8") (pintype "passive"))
    )
    (net (code "93") (name "Net-(C16-Pad1)") (class "Default")
      (node (ref "C16") (pin "1") (pinfunction "1_1") (pintype "passive"))
      (node (ref "R10") (pin "2") (pinfunction "2_2") (pintype "passive"))
    )
    (net (code "94") (name "Net-(C17-Pad1)") (class "Default")
      (node (ref "C17") (pin "1") (pinfunction "1_1") (pintype "passive"))
      (node (ref "R11") (pin "2") (pinfunction "2_2") (pintype "passive"))
    )
    (net (code "95") (name "Net-(D1-A)") (class "Default")
      (node (ref "D1") (pin "1") (pinfunction "A_1") (pintype "passive"))
      (node (ref "R1") (pin "1") (pinfunction "1_1") (pintype "passive"))
    )
    (net (code "96") (name "Net-(D2-A)") (class "Default")
      (node (ref "D2") (pin "1") (pinfunction "A_1") (pintype "passive"))
      (node (ref "R2") (pin "1") (pinfunction "1_1") (pintype "passive"))
    )
    (net (code "97") (name "Net-(D3-A)") (class "Default")
      (node (ref "D3") (pin "1") (pinfunction "A_1") (pintype "passive"))
      (node (ref "P4") (pin "2") (pinfunction "2_2") (pintype "passive"))
      (node (ref "Q1") (pin "C") (pintype "passive"))
      (node (ref "R38") (pin "1") (pinfunction "1_1") (pintype "passive"))
    )
    (net (code "98") (name "Net-(D4-K)") (class "Default")
      (node (ref "D4") (pin "2") (pinfunction "K_2") (pintype "passive"))
      (node (ref "L1") (pin "1") (pinfunction "1_1") (pintype "passive"))
      (node (ref "U1") (pin "2") (pinfunction "Vout_2") (pintype "passive"))
    )
    (net (code "99") (name "Net-(D9-A)") (class "Default")
      (node (ref "D9") (pin "1") (pinfunction "A_1") (pintype "passive"))
      (node (ref "R8") (pin "1") (pinfunction "1_1") (pintype "passive"))
    )
    (net (code "100") (name "Net-(D11-A)") (class "Default")
      (node (ref "D11") (pin "1") (pinfunction "A_1") (pintype "passive"))
      (node (ref "R13") (pin "1") (pinfunction "1_1") (pintype "passive"))
    )
    (net (code "101") (name "Net-(D11-K)") (class "Default")
      (node (ref "D11") (pin "2") (pinfunction "K_2") (pintype "passive"))
      (node (ref "JP1") (pin "5") (pinfunction "5_5") (pintype "passive"))
    )
    (net (code "102") (name "Net-(D12-A)") (class "Default")
      (node (ref "D12") (pin "1") (pinfunction "A_1") (pintype "passive"))
      (node (ref "R15") (pin "1") (pinfunction "1_1") (pintype "passive"))
    )
    (net (code "103") (name "Net-(D12-K)") (class "Default")
      (node (ref "D12") (pin "2") (pinfunction "K_2") (pintype "passive"))
      (node (ref "JP1") (pin "6") (pinfunction "6_6") (pintype "passive"))
    )
    (net (code "104") (name "Net-(D13-A)") (class "Default")
      (node (ref "D13") (pin "1") (pinfunction "A_1") (pintype "passive"))
      (node (ref "R59") (pin "1") (pinfunction "1_1") (pintype "passive"))
    )
    (net (code "105") (name "Net-(D14-A)") (class "Default")
      (node (ref "D14") (pin "1") (pinfunction "A_1") (pintype "passive"))
      (node (ref "R60") (pin "1") (pinfunction "1_1") (pintype "passive"))
    )
    (net (code "106") (name "Net-(D15-A)") (class "Default")
      (node (ref "D15") (pin "1") (pinfunction "A_1") (pintype "passive"))
      (node (ref "R61") (pin "1") (pinfunction "1_1") (pintype "passive"))
    )
    (net (code "107") (name "Net-(D16-A)") (class "Default")
      (node (ref "D16") (pin "1") (pinfunction "A_1") (pintype "passive"))
      (node (ref "R87") (pin "1") (pinfunction "1_1") (pintype "passive"))
    )
    (net (code "108") (name "Net-(D17-A)") (class "Default")
      (node (ref "D17") (pin "1") (pinfunction "A_1") (pintype "passive"))
      (node (ref "R88") (pin "1") (pinfunction "1_1") (pintype "passive"))
    )
    (net (code "109") (name "Net-(D18-A)") (class "Default")
      (node (ref "D18") (pin "1") (pinfunction "A_1") (pintype "passive"))
      (node (ref "R89") (pin "1") (pinfunction "1_1") (pintype "passive"))
    )
    (net (code "110") (name "Net-(DB1-V+)") (class "Default")
      (node (ref "C1") (pin "2") (pinfunction "2_2") (pintype "passive"))
      (node (ref "C2") (pin "1") (pinfunction "1_1") (pintype "passive"))
      (node (ref "DB1") (pin "3") (pinfunction "V+_3") (pintype "passive"))
      (node (ref "TM1") (pin "1") (pinfunction "Vin_1") (pintype "passive"))
      (node (ref "U1") (pin "1") (pinfunction "Vin_1") (pintype "passive"))
    )
    (net (code "111") (name "Net-(IC1-A+)") (class "Default")
      (node (ref "IC1") (pin "6") (pinfunction "A+_6") (pintype "passive"))
      (node (ref "R100") (pin "1") (pinfunction "1_1") (pintype "passive"))
      (node (ref "R98") (pin "2") (pinfunction "2_2") (pintype "passive"))
    )
    (net (code "112") (name "Net-(IC1-B-)") (class "Default")
      (node (ref "IC1") (pin "7") (pinfunction "B-_7") (pintype "passive"))
      (node (ref "R97") (pin "1") (pinfunction "1_1") (pintype "passive"))
      (node (ref "R98") (pin "1") (pinfunction "1_1") (pintype "passive"))
    )
    (net (code "113") (name "Net-(J6-Pad2)") (class "Default")
      (node (ref "J6") (pin "2") (pinfunction "2_2") (pintype "passive"))
      (node (ref "J6") (pin "7") (pinfunction "7_7") (pintype "passive"))
      (node (ref "R27") (pin "1") (pinfunction "1_1") (pintype "passive"))
    )
    (net (code "114") (name "Net-(J6-Pad4)") (class "Default")
      (node (ref "J6") (pin "4") (pinfunction "4_4") (pintype "passive"))
      (node (ref "J6") (pin "8") (pinfunction "8_8") (pintype "passive"))
      (node (ref "R42") (pin "1") (pinfunction "1_1") (pintype "passive"))
    )
    (net (code "115") (name "Net-(J6-Pad5)") (class "Default")
      (node (ref "J6") (pin "5") (pinfunction "5_5") (pintype "passive"))
      (node (ref "K10") (pin "2") (pinfunction "2_2") (pintype "passive"))
      (node (ref "K10") (pin "4") (pinfunction "4_4") (pintype "passive"))
      (node (ref "R57") (pin "1") (pinfunction "1_1") (pintype "passive"))
    )
    (net (code "116") (name "Net-(J6-Pad10)") (class "Default")
      (node (ref "J6") (pin "10") (pinfunction "10_10") (pintype "passive"))
      (node (ref "K9") (pin "2") (pinfunction "2_2") (pintype "passive"))
      (node (ref "K9") (pin "4") (pinfunction "4_4") (pintype "passive"))
    )
    (net (code "117") (name "Net-(J6-Pad11)") (class "Default")
      (node (ref "J6") (pin "11") (pinfunction "11_11") (pintype "passive"))
      (node (ref "J6") (pin "6") (pinfunction "6_6") (pintype "passive"))
      (node (ref "R4") (pin "1") (pinfunction "1_1") (pintype "passive"))
    )
    (net (code "118") (name "Net-(J6-Pad12)") (class "Default")
      (node (ref "J6") (pin "12") (pinfunction "12_12") (pintype "passive"))
      (node (ref "K11") (pin "1") (pinfunction "1_1") (pintype "passive"))
      (node (ref "K11") (pin "3") (pinfunction "3_3") (pintype "passive"))
      (node (ref "K9") (pin "1") (pinfunction "1_1") (pintype "passive"))
      (node (ref "K9") (pin "3") (pinfunction "3_3") (pintype "passive"))
      (node (ref "R6") (pin "1") (pinfunction "1_1") (pintype "passive"))
    )
    (net (code "119") (name "Net-(J6-Pad13)") (class "Default")
      (node (ref "J6") (pin "13") (pinfunction "13_13") (pintype "passive"))
      (node (ref "K10") (pin "1") (pinfunction "1_1") (pintype "passive"))
      (node (ref "K10") (pin "3") (pinfunction "3_3") (pintype "passive"))
    )
    (net (code "120") (name "Net-(J6-Pad15)") (class "Default")
      (node (ref "J6") (pin "15") (pinfunction "15_15") (pintype "passive"))
      (node (ref "K11") (pin "2") (pinfunction "2_2") (pintype "passive"))
      (node (ref "K11") (pin "4") (pinfunction "4_4") (pintype "passive"))
    )
    (net (code "121") (name "Net-(J7-Pad2)") (class "Default")
      (node (ref "J7") (pin "2") (pinfunction "2_2") (pintype "passive"))
      (node (ref "J7") (pin "7") (pinfunction "7_7") (pintype "passive"))
      (node (ref "R65") (pin "1") (pinfunction "1_1") (pintype "passive"))
    )
    (net (code "122") (name "Net-(J7-Pad4)") (class "Default")
      (node (ref "J7") (pin "4") (pinfunction "4_4") (pintype "passive"))
      (node (ref "J7") (pin "8") (pinfunction "8_8") (pintype "passive"))
      (node (ref "R80") (pin "1") (pinfunction "1_1") (pintype "passive"))
    )
    (net (code "123") (name "Net-(J7-Pad5)") (class "Default")
      (node (ref "J7") (pin "5") (pinfunction "5_5") (pintype "passive"))
      (node (ref "K13") (pin "2") (pinfunction "2_2") (pintype "passive"))
      (node (ref "K13") (pin "4") (pinfunction "4_4") (pintype "passive"))
      (node (ref "R85") (pin "1") (pinfunction "1_1") (pintype "passive"))
    )
    (net (code "124") (name "Net-(J7-Pad10)") (class "Default")
      (node (ref "J7") (pin "10") (pinfunction "10_10") (pintype "passive"))
      (node (ref "K12") (pin "2") (pinfunction "2_2") (pintype "passive"))
      (node (ref "K12") (pin "4") (pinfunction "4_4") (pintype "passive"))
    )
    (net (code "125") (name "Net-(J7-Pad11)") (class "Default")
      (node (ref "J7") (pin "11") (pinfunction "11_11") (pintype "passive"))
      (node (ref "J7") (pin "6") (pinfunction "6_6") (pintype "passive"))
      (node (ref "R70") (pin "1") (pinfunction "1_1") (pintype "passive"))
    )
    (net (code "126") (name "Net-(J7-Pad12)") (class "Default")
      (node (ref "J7") (pin "12") (pinfunction "12_12") (pintype "passive"))
      (node (ref "K12") (pin "1") (pinfunction "1_1") (pintype "passive"))
      (node (ref "K12") (pin "3") (pinfunction "3_3") (pintype "passive"))
      (node (ref "K14") (pin "1") (pinfunction "1_1") (pintype "passive"))
      (node (ref "K14") (pin "3") (pinfunction "3_3") (pintype "passive"))
      (node (ref "R75") (pin "1") (pinfunction "1_1") (pintype "passive"))
    )
    (net (code "127") (name "Net-(J7-Pad13)") (class "Default")
      (node (ref "J7") (pin "13") (pinfunction "13_13") (pintype "passive"))
      (node (ref "K13") (pin "1") (pinfunction "1_1") (pintype "passive"))
      (node (ref "K13") (pin "3") (pinfunction "3_3") (pintype "passive"))
    )
    (net (code "128") (name "Net-(J7-Pad15)") (class "Default")
      (node (ref "J7") (pin "15") (pinfunction "15_15") (pintype "passive"))
      (node (ref "K14") (pin "2") (pinfunction "2_2") (pintype "passive"))
      (node (ref "K14") (pin "4") (pinfunction "4_4") (pintype "passive"))
    )
    (net (code "129") (name "Net-(JP4-Pad2)") (class "Default")
      (node (ref "JP4") (pin "2") (pinfunction "2_2") (pintype "passive"))
      (node (ref "JP6") (pin "2") (pinfunction "2_2") (pintype "passive"))
      (node (ref "R100") (pin "2") (pinfunction "2_2") (pintype "passive"))
    )
    (net (code "130") (name "Net-(JP4-Pad3)") (class "Default")
      (node (ref "JP4") (pin "3") (pinfunction "3_3") (pintype "passive"))
      (node (ref "JP6") (pin "3") (pinfunction "3_3") (pintype "passive"))
      (node (ref "R97") (pin "2") (pinfunction "2_2") (pintype "passive"))
    )
    (net (code "131") (name "Net-(M1-EN)") (class "Default")
      (node (ref "M1") (pin "3") (pinfunction "EN_3") (pintype "passive"))
      (node (ref "R23") (pin "1") (pinfunction "1_1") (pintype "passive"))
    )
    (net (code "132") (name "Net-(M1-GPIO0)") (class "Default")
      (node (ref "M1") (pin "12") (pinfunction "GPIO0_12") (pintype "passive"))
      (node (ref "P18") (pin "1") (pinfunction "1_1") (pintype "passive"))
    )
    (net (code "133") (name "Net-(M1-GPIO2)") (class "Default")
      (node (ref "M1") (pin "11") (pinfunction "GPIO2_11") (pintype "passive"))
      (node (ref "R26") (pin "2") (pinfunction "2_2") (pintype "passive"))
    )
    (net (code "134") (name "Net-(M1-RST)") (class "Default")
      (node (ref "M1") (pin "1") (pinfunction "RST_1") (pintype "passive"))
      (node (ref "R21") (pin "1") (pinfunction "1_1") (pintype "passive"))
    )
    (net (code "135") (name "Net-(M1-RXD0)") (class "Default")
      (node (ref "M1") (pin "15") (pinfunction "RXD0_15") (pintype "passive"))
      (node (ref "R35") (pin "2") (pinfunction "2_2") (pintype "passive"))
    )
    (net (code "136") (name "Net-(M1-TXD0)") (class "Default")
      (node (ref "M1") (pin "16") (pinfunction "TXD0_16") (pintype "passive"))
      (node (ref "R30") (pin "2") (pinfunction "2_2") (pintype "passive"))
    )
    (net (code "137") (name "Net-(P2-LED_Anode)") (class "Default")
      (node (ref "P2") (pin "1") (pinfunction "LED_Anode_1") (pintype "passive"))
      (node (ref "R13") (pin "2") (pinfunction "2_2") (pintype "passive"))
    )
    (net (code "138") (name "Net-(P2-LED_Cathode)") (class "Default")
      (node (ref "JP1") (pin "7") (pinfunction "7_7") (pintype "passive"))
      (node (ref "P2") (pin "2") (pinfunction "LED_Cathode_2") (pintype "passive"))
      (node (ref "P3") (pin "2") (pinfunction "LED_Cathode_2") (pintype "passive"))
    )
    (net (code "139") (name "Net-(P3-LED_Anode)") (class "Default")
      (node (ref "P3") (pin "1") (pinfunction "LED_Anode_1") (pintype "passive"))
      (node (ref "R15") (pin "2") (pinfunction "2_2") (pintype "passive"))
    )
    (net (code "140") (name "Net-(P5-LED_Anode)") (class "Default")
      (node (ref "P5") (pin "1") (pinfunction "LED_Anode_1") (pintype "passive"))
      (node (ref "R27") (pin "2") (pinfunction "2_2") (pintype "passive"))
    )
    (net (code "141") (name "Net-(P6-LED_Anode)") (class "Default")
      (node (ref "P6") (pin "1") (pinfunction "LED_Anode_1") (pintype "passive"))
      (node (ref "R4") (pin "2") (pinfunction "2_2") (pintype "passive"))
    )
    (net (code "142") (name "Net-(P7-LED_Anode)") (class "Default")
      (node (ref "P7") (pin "1") (pinfunction "LED_Anode_1") (pintype "passive"))
      (node (ref "R6") (pin "2") (pinfunction "2_2") (pintype "passive"))
    )
    (net (code "143") (name "Net-(P8-LED_Anode)") (class "Default")
      (node (ref "P8") (pin "1") (pinfunction "LED_Anode_1") (pintype "passive"))
      (node (ref "R42") (pin "2") (pinfunction "2_2") (pintype "passive"))
    )
    (net (code "144") (name "Net-(P9-LED_Anode)") (class "Default")
      (node (ref "P9") (pin "1") (pinfunction "LED_Anode_1") (pintype "passive"))
      (node (ref "R57") (pin "2") (pinfunction "2_2") (pintype "passive"))
    )
    (net (code "145") (name "Net-(P10-LED_Anode)") (class "Default")
      (node (ref "P10") (pin "1") (pinfunction "LED_Anode_1") (pintype "passive"))
      (node (ref "R65") (pin "2") (pinfunction "2_2") (pintype "passive"))
    )
    (net (code "146") (name "Net-(P11-LED_Anode)") (class "Default")
      (node (ref "P11") (pin "1") (pinfunction "LED_Anode_1") (pintype "passive"))
      (node (ref "R70") (pin "2") (pinfunction "2_2") (pintype "passive"))
    )
    (net (code "147") (name "Net-(P12-LED_Anode)") (class "Default")
      (node (ref "P12") (pin "1") (pinfunction "LED_Anode_1") (pintype "passive"))
      (node (ref "R75") (pin "2") (pinfunction "2_2") (pintype "passive"))
    )
    (net (code "148") (name "Net-(P13-LED_Anode)") (class "Default")
      (node (ref "P13") (pin "1") (pinfunction "LED_Anode_1") (pintype "passive"))
      (node (ref "R80") (pin "2") (pinfunction "2_2") (pintype "passive"))
    )
    (net (code "149") (name "Net-(P14-LED_Anode)") (class "Default")
      (node (ref "P14") (pin "1") (pinfunction "LED_Anode_1") (pintype "passive"))
      (node (ref "R85") (pin "2") (pinfunction "2_2") (pintype "passive"))
    )
    (net (code "150") (name "Net-(P17-Pad1)") (class "Default")
      (node (ref "P17") (pin "1") (pinfunction "1_1") (pintype "passive"))
      (node (ref "R30") (pin "1") (pinfunction "1_1") (pintype "passive"))
    )
    (net (code "151") (name "Net-(P17-Pad3)") (class "Default")
      (node (ref "P17") (pin "3") (pinfunction "3_3") (pintype "passive"))
      (node (ref "R35") (pin "1") (pinfunction "1_1") (pintype "passive"))
    )
    (net (code "152") (name "Net-(P19-Pad1)") (class "Default")
      (node (ref "P19") (pin "1") (pinfunction "1_1") (pintype "passive"))
      (node (ref "R37") (pin "1") (pinfunction "1_1") (pintype "passive"))
    )
    (net (code "153") (name "Net-(P19-Pad2)") (class "Default")
      (node (ref "P19") (pin "2") (pinfunction "2_2") (pintype "passive"))
      (node (ref "R39") (pin "1") (pinfunction "1_1") (pintype "passive"))
    )
    (net (code "154") (name "Net-(Q1-PadB)") (class "Default")
      (node (ref "Q1") (pin "B") (pintype "passive"))
      (node (ref "R40") (pin "2") (pinfunction "2_2") (pintype "passive"))
      (node (ref "R43") (pin "2") (pinfunction "2_2") (pintype "passive"))
    )
    (net (code "155") (name "Net-(U20-X1)") (class "Default")
      (node (ref "U20") (pin "2") (pinfunction "X1_2") (pintype "passive"))
      (node (ref "Y1") (pin "1") (pinfunction "1_1") (pintype "passive"))
    )
    (net (code "156") (name "Net-(U20-X2)") (class "Default")
      (node (ref "U20") (pin "3") (pinfunction "X2_3") (pintype "passive"))
      (node (ref "Y1") (pin "2") (pinfunction "2_2") (pintype "passive"))
    )
    (net (code "157") (name "VCC") (class "Default")
      (node (ref "C10") (pin "1") (pinfunction "1_1") (pintype "passive"))
      (node (ref "C20") (pin "2") (pinfunction "2_2") (pintype "passive"))
      (node (ref "C21") (pin "2") (pinfunction "2_2") (pintype "passive"))
      (node (ref "C22") (pin "2") (pinfunction "2_2") (pintype "passive"))
      (node (ref "C23") (pin "2") (pinfunction "2_2") (pintype "passive"))
      (node (ref "C25") (pin "1") (pinfunction "1_1") (pintype "passive"))
      (node (ref "C26") (pin "1") (pinfunction "1_1") (pintype "passive"))
      (node (ref "C27") (pin "2") (pinfunction "2_2") (pintype "passive"))
      (node (ref "C28") (pin "2") (pinfunction "2_2") (pintype "passive"))
      (node (ref "C3") (pin "1") (pinfunction "1_1") (pintype "passive"))
      (node (ref "C34") (pin "1") (pinfunction "1_1") (pintype "passive"))
      (node (ref "D19") (pin "2") (pinfunction "K_2") (pintype "passive"))
      (node (ref "IC1") (pin "8") (pinfunction "VCC_8") (pintype "passive"))
      (node (ref "JP3") (pin "18") (pinfunction "18_18") (pintype "passive"))
      (node (ref "JP3") (pin "19") (pinfunction "19_19") (pintype "passive"))
      (node (ref "JP3") (pin "20") (pinfunction "20_20") (pintype "passive"))
      (node (ref "JP5") (pin "2") (pinfunction "2_2") (pintype "passive"))
      (node (ref "L1") (pin "2") (pinfunction "2_2") (pintype "passive"))
      (node (ref "L2") (pin "2") (pinfunction "2_2") (pintype "passive"))
      (node (ref "P15") (pin "3") (pinfunction "3_3") (pintype "passive"))
      (node (ref "P16") (pin "3") (pinfunction "3_3") (pintype "passive"))
      (node (ref "R1") (pin "2") (pinfunction "2_2") (pintype "passive"))
      (node (ref "R12") (pin "1") (pinfunction "1_1") (pintype "passive"))
      (node (ref "R14") (pin "1") (pinfunction "1_1") (pintype "passive"))
      (node (ref "R28") (pin "2") (pinfunction "2_2") (pintype "passive"))
      (node (ref "R3") (pin "2") (pinfunction "2_2") (pintype "passive"))
      (node (ref "R31") (pin "2") (pinfunction "2_2") (pintype "passive"))
      (node (ref "R32") (pin "2") (pinfunction "2_2") (pintype "passive"))
      (node (ref "R33") (pin "2") (pinfunction "2_2") (pintype "passive"))
      (node (ref "R34") (pin "2") (pinfunction "2_2") (pintype "passive"))
      (node (ref "R36") (pin "2") (pinfunction "2_2") (pintype "passive"))
      (node (ref "R41") (pin "2") (pinfunction "2_2") (pintype "passive"))
      (node (ref "R5") (pin "2") (pinfunction "2_2") (pintype "passive"))
      (node (ref "R56") (pin "2") (pinfunction "2_2") (pintype "passive"))
      (node (ref "R64") (pin "2") (pinfunction "2_2") (pintype "passive"))
      (node (ref "R69") (pin "2") (pinfunction "2_2") (pintype "passive"))
      (node (ref "R74") (pin "2") (pinfunction "2_2") (pintype "passive"))
      (node (ref "R79") (pin "2") (pinfunction "2_2") (pintype "passive"))
      (node (ref "R84") (pin "2") (pinfunction "2_2") (pintype "passive"))
      (node (ref "R96") (pin "2") (pinfunction "2_2") (pintype "passive"))
      (node (ref "U1") (pin "4") (pinfunction "Feedback_4") (pintype "passive"))
      (node (ref "U20") (pin "1") (pinfunction "Vcc2_1") (pintype "passive"))
      (node (ref "U21") (pin "8") (pinfunction "VCC_8") (pintype "passive"))
      (node (ref "U3") (pin "10") (pinfunction "VCC_10") (pintype "passive"))
      (node (ref "U3") (pin "31") (pinfunction "VCC_31") (pintype "passive"))
      (node (ref "U3") (pin "61") (pinfunction "VCC_61") (pintype "passive"))
      (node (ref "U3") (pin "80") (pinfunction "VCC_80") (pintype "passive"))
      (node (ref "U5") (pin "3") (pinfunction "In_3") (pintype "passive"))
    )
    (net (code "158") (name "unconnected-(J3-Pad3)") (class "Default")
      (node (ref "J3") (pin "3") (pinfunction "3_3") (pintype "passive+no_connect"))
    )
    (net (code "159") (name "unconnected-(J4-Pad2)") (class "Default")
      (node (ref "J4") (pin "2") (pinfunction "2_2") (pintype "passive+no_connect"))
    )
    (net (code "160") (name "unconnected-(JP5-Pad3)") (class "Default")
      (node (ref "JP5") (pin "3") (pinfunction "3_3") (pintype "passive+no_connect"))
    )
    (net (code "161") (name "unconnected-(JP5-Pad4)") (class "Default")
      (node (ref "JP5") (pin "4") (pinfunction "4_4") (pintype "passive+no_connect"))
    )
    (net (code "162") (name "unconnected-(JP5-Pad6)") (class "Default")
      (node (ref "JP5") (pin "6") (pinfunction "6_6") (pintype "passive+no_connect"))
    )
    (net (code "163") (name "unconnected-(JP5-Pad8)") (class "Default")
      (node (ref "JP5") (pin "8") (pinfunction "8_8") (pintype "passive+no_connect"))
    )
    (net (code "164") (name "unconnected-(M1-ADC-Pad2)") (class "Default")
      (node (ref "M1") (pin "2") (pinfunction "ADC_2") (pintype "passive+no_connect"))
    )
    (net (code "165") (name "unconnected-(M1-GPIO4-Pad13)") (class "Default")
      (node (ref "M1") (pin "13") (pinfunction "GPIO4_13") (pintype "passive"))
    )
    (net (code "166") (name "unconnected-(M1-GPIO5-Pad14)") (class "Default")
      (node (ref "M1") (pin "14") (pinfunction "GPIO5_14") (pintype "passive"))
    )
    (net (code "167") (name "unconnected-(M1-GPIO12-Pad6)") (class "Default")
      (node (ref "M1") (pin "6") (pinfunction "GPIO12_6") (pintype "passive+no_connect"))
    )
    (net (code "168") (name "unconnected-(M1-GPIO13-Pad7)") (class "Default")
      (node (ref "M1") (pin "7") (pinfunction "GPIO13_7") (pintype "passive+no_connect"))
    )
    (net (code "169") (name "unconnected-(M1-GPIO14-Pad5)") (class "Default")
      (node (ref "M1") (pin "5") (pinfunction "GPIO14_5") (pintype "passive+no_connect"))
    )
    (net (code "170") (name "unconnected-(M1-GPIO16-Pad4)") (class "Default")
      (node (ref "M1") (pin "4") (pinfunction "GPIO16_4") (pintype "passive+no_connect"))
    )
    (net (code "171") (name "unconnected-(P15-Pad1)") (class "Default")
      (node (ref "P15") (pin "1") (pinfunction "1_1") (pintype "passive"))
    )
    (net (code "172") (name "unconnected-(P16-Pad2)") (class "Default")
      (node (ref "P16") (pin "2") (pinfunction "2_2") (pintype "passive"))
    )
    (net (code "173") (name "unconnected-(U2-IN7-Pad7)") (class "Default")
      (node (ref "U2") (pin "7") (pinfunction "IN7_7") (pintype "passive"))
    )
    (net (code "174") (name "unconnected-(U2-IN8-Pad8)") (class "Default")
      (node (ref "U2") (pin "8") (pinfunction "IN8_8") (pintype "passive"))
    )
    (net (code "175") (name "unconnected-(U2-OT1-Pad18)") (class "Default")
      (node (ref "U2") (pin "18") (pinfunction "OT1_18") (pintype "passive"))
    )
    (net (code "176") (name "unconnected-(U2-OT7-Pad12)") (class "Default")
      (node (ref "U2") (pin "12") (pinfunction "OT7_12") (pintype "passive"))
    )
    (net (code "177") (name "unconnected-(U2-OT8-Pad11)") (class "Default")
      (node (ref "U2") (pin "11") (pinfunction "OT8_11") (pintype "passive"))
    )
    (net (code "178") (name "unconnected-(U3-PA0-Pad78)") (class "Default")
      (node (ref "U3") (pin "78") (pinfunction "PA0_78") (pintype "passive"))
    )
    (net (code "179") (name "unconnected-(U3-PA1-Pad77)") (class "Default")
      (node (ref "U3") (pin "77") (pinfunction "PA1_77") (pintype "passive"))
    )
    (net (code "180") (name "unconnected-(U3-PA2-Pad76)") (class "Default")
      (node (ref "U3") (pin "76") (pinfunction "PA2_76") (pintype "passive"))
    )
    (net (code "181") (name "unconnected-(U3-PA7-Pad71)") (class "Default")
      (node (ref "U3") (pin "71") (pinfunction "PA7_71") (pintype "passive"))
    )
    (net (code "182") (name "unconnected-(U3-PB4-Pad23)") (class "Default")
      (node (ref "U3") (pin "23") (pinfunction "PB4_23") (pintype "passive"))
    )
    (net (code "183") (name "unconnected-(U3-PB5-Pad24)") (class "Default")
      (node (ref "U3") (pin "24") (pinfunction "PB5_24") (pintype "passive"))
    )
    (net (code "184") (name "unconnected-(U3-PB6-Pad25)") (class "Default")
      (node (ref "U3") (pin "25") (pinfunction "PB6_25") (pintype "passive"))
    )
    (net (code "185") (name "unconnected-(U3-PB7-Pad26)") (class "Default")
      (node (ref "U3") (pin "26") (pinfunction "PB7_26") (pintype "passive"))
    )
    (net (code "186") (name "unconnected-(U3-PC7-Pad60)") (class "Default")
      (node (ref "U3") (pin "60") (pinfunction "PC7_60") (pintype "passive"))
    )
    (net (code "187") (name "unconnected-(U3-PF0(ADC0)-Pad97)") (class "Default")
      (node (ref "U3") (pin "97") (pinfunction "PF0(ADC0)_97") (pintype "passive"))
    )
    (net (code "188") (name "unconnected-(U3-PF1(ADC1)-Pad96)") (class "Default")
      (node (ref "U3") (pin "96") (pinfunction "PF1(ADC1)_96") (pintype "passive"))
    )
    (net (code "189") (name "unconnected-(U3-PF2(ADC2)-Pad95)") (class "Default")
      (node (ref "U3") (pin "95") (pinfunction "PF2(ADC2)_95") (pintype "passive"))
    )
    (net (code "190") (name "unconnected-(U3-PF3(ADC3)-Pad94)") (class "Default")
      (node (ref "U3") (pin "94") (pinfunction "PF3(ADC3)_94") (pintype "passive"))
    )
    (net (code "191") (name "unconnected-(U3-PF4(ADC4)-Pad93)") (class "Default")
      (node (ref "U3") (pin "93") (pinfunction "PF4(ADC4)_93") (pintype "passive"))
    )
    (net (code "192") (name "unconnected-(U3-PF5(ADC5)-Pad92)") (class "Default")
      (node (ref "U3") (pin "92") (pinfunction "PF5(ADC5)_92") (pintype "passive"))
    )
    (net (code "193") (name "unconnected-(U3-PF6(ADC6)-Pad91)") (class "Default")
      (node (ref "U3") (pin "91") (pinfunction "PF6(ADC6)_91") (pintype "passive"))
    )
    (net (code "194") (name "unconnected-(U3-PF7(ADC7)-Pad90)") (class "Default")
      (node (ref "U3") (pin "90") (pinfunction "PF7(ADC7)_90") (pintype "passive"))
    )
    (net (code "195") (name "unconnected-(U3-PG2-Pad70)") (class "Default")
      (node (ref "U3") (pin "70") (pinfunction "PG2_70") (pintype "passive"))
    )
    (net (code "196") (name "unconnected-(U3-PG3-Pad28)") (class "Default")
      (node (ref "U3") (pin "28") (pinfunction "PG3_28") (pintype "passive"))
    )
    (net (code "197") (name "unconnected-(U3-PG4-Pad29)") (class "Default")
      (node (ref "U3") (pin "29") (pinfunction "PG4_29") (pintype "passive"))
    )
    (net (code "198") (name "unconnected-(U3-PH7-Pad27)") (class "Default")
      (node (ref "U3") (pin "27") (pinfunction "PH7_27") (pintype "passive"))
    )
    (net (code "199") (name "unconnected-(U3-PJ7-Pad79)") (class "Default")
      (node (ref "U3") (pin "79") (pinfunction "PJ7_79") (pintype "passive+no_connect"))
    )
    (net (code "200") (name "unconnected-(U3-PK0(ADC8)-Pad89)") (class "Default")
      (node (ref "U3") (pin "89") (pinfunction "PK0(ADC8)_89") (pintype "passive"))
    )
    (net (code "201") (name "unconnected-(U3-PK1(ADC9)-Pad88)") (class "Default")
      (node (ref "U3") (pin "88") (pinfunction "PK1(ADC9)_88") (pintype "passive"))
    )
    (net (code "202") (name "unconnected-(U3-PK2(ADC10)-Pad87)") (class "Default")
      (node (ref "U3") (pin "87") (pinfunction "PK2(ADC10)_87") (pintype "passive"))
    )
    (net (code "203") (name "unconnected-(U3-PK3(ADC11)-Pad86)") (class "Default")
      (node (ref "U3") (pin "86") (pinfunction "PK3(ADC11)_86") (pintype "passive"))
    )
    (net (code "204") (name "unconnected-(U3-PK4(ADC12)-Pad85)") (class "Default")
      (node (ref "U3") (pin "85") (pinfunction "PK4(ADC12)_85") (pintype "passive"))
    )
    (net (code "205") (name "unconnected-(U4-IN1-Pad1)") (class "Default")
      (node (ref "U4") (pin "1") (pinfunction "IN1_1") (pintype "passive"))
    )
    (net (code "206") (name "unconnected-(U4-IN2-Pad2)") (class "Default")
      (node (ref "U4") (pin "2") (pinfunction "IN2_2") (pintype "passive"))
    )
    (net (code "207") (name "unconnected-(U4-IN3-Pad3)") (class "Default")
      (node (ref "U4") (pin "3") (pinfunction "IN3_3") (pintype "passive"))
    )
    (net (code "208") (name "unconnected-(U4-IN4-Pad4)") (class "Default")
      (node (ref "U4") (pin "4") (pinfunction "IN4_4") (pintype "passive"))
    )
    (net (code "209") (name "unconnected-(U4-OT1-Pad18)") (class "Default")
      (node (ref "U4") (pin "18") (pinfunction "OT1_18") (pintype "passive"))
    )
    (net (code "210") (name "unconnected-(U4-OT2-Pad17)") (class "Default")
      (node (ref "U4") (pin "17") (pinfunction "OT2_17") (pintype "passive"))
    )
    (net (code "211") (name "unconnected-(U4-OT3-Pad16)") (class "Default")
      (node (ref "U4") (pin "16") (pinfunction "OT3_16") (pintype "power_in"))
    )
    (net (code "212") (name "unconnected-(U4-OT4-Pad15)") (class "Default")
      (node (ref "U4") (pin "15") (pinfunction "OT4_15") (pintype "passive"))
    )
    (net (code "213") (name "unconnected-(U5-TAB-Pad4)") (class "Default")
      (node (ref "U5") (pin "4") (pinfunction "TAB_4") (pintype "passive"))
    )
    (net (code "214") (name "unconnected-(U12-NC-Pad6)") (class "Default")
      (node (ref "U12") (pin "6") (pinfunction "NC_6") (pintype "passive+no_connect"))
    )
    (net (code "215") (name "unconnected-(U13-NC-Pad6)") (class "Default")
      (node (ref "U13") (pin "6") (pinfunction "NC_6") (pintype "passive+no_connect"))
    )
  )
)
